# matrix_main_board.net
KiCad netlist of a schematic drawn in EAGLE
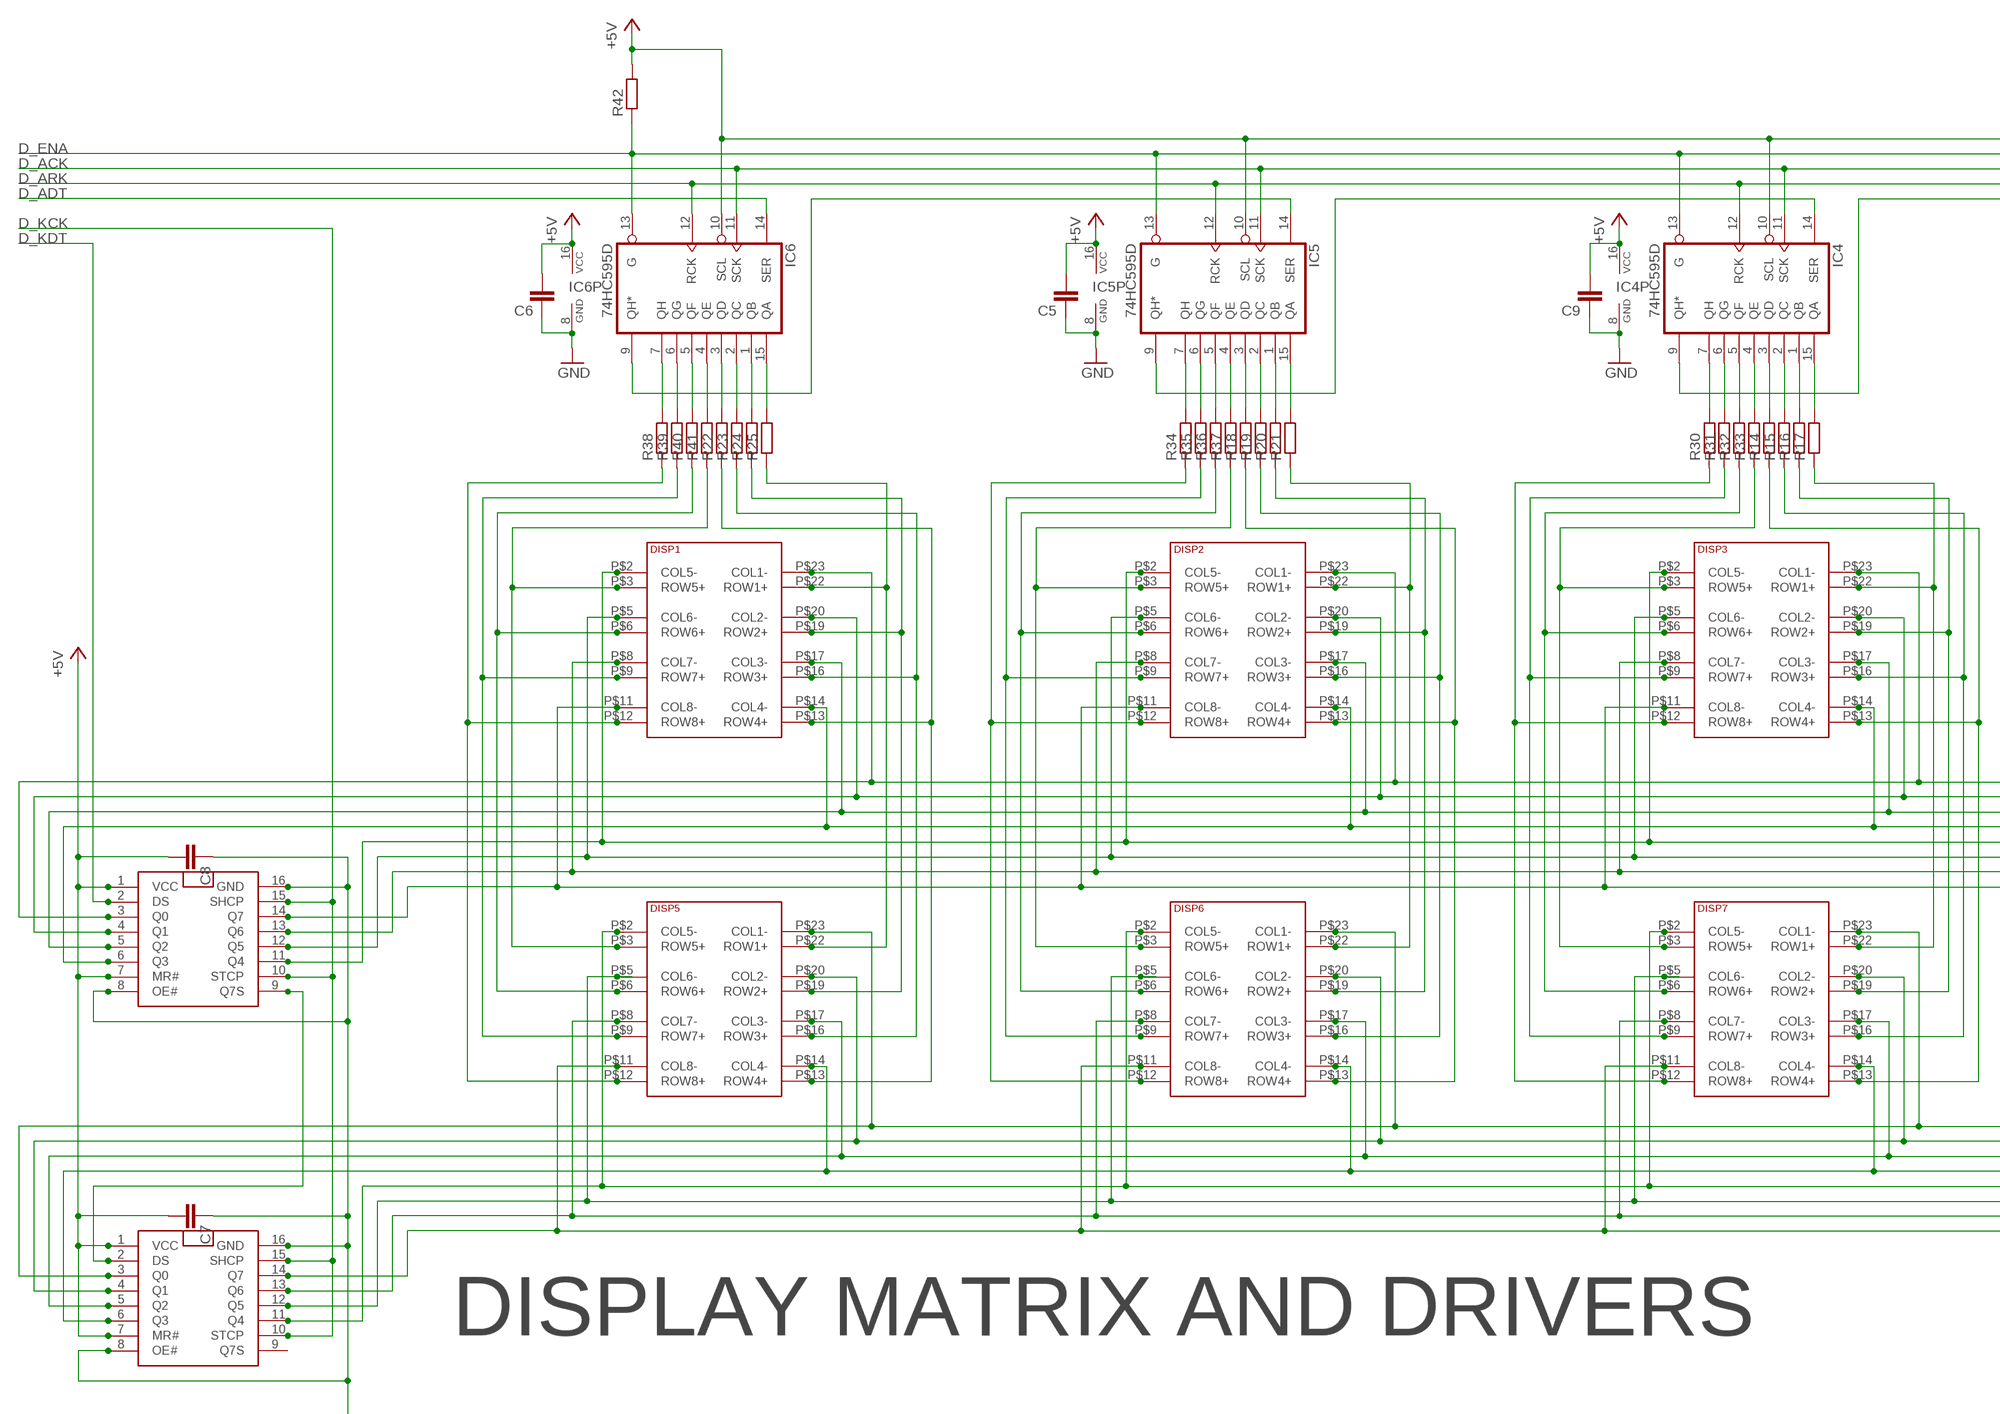
[diagram p0: schematic, sheet 1, part 1 of 3]
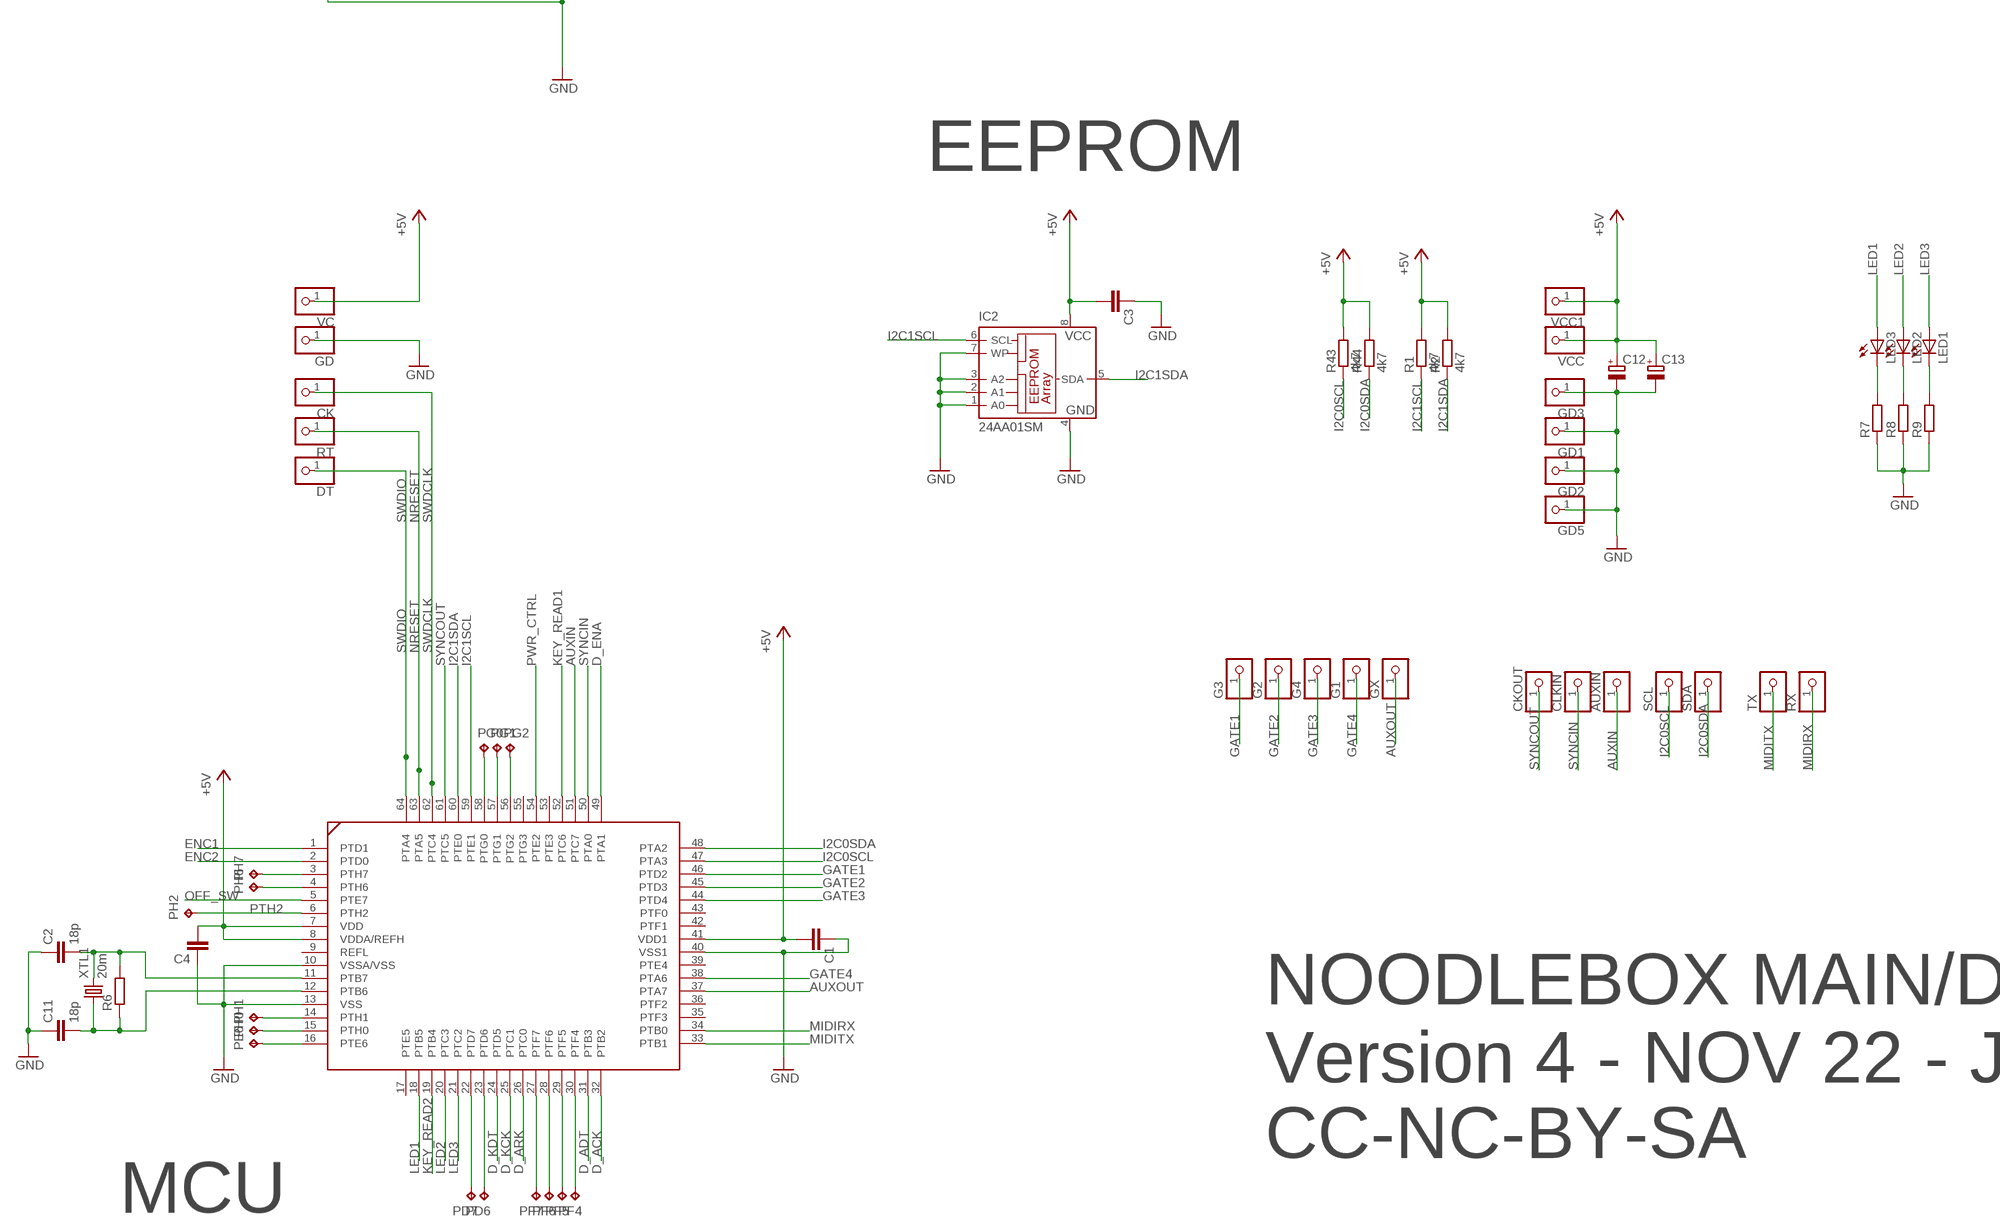
[diagram p1: schematic, sheet 1, part 2 of 3]
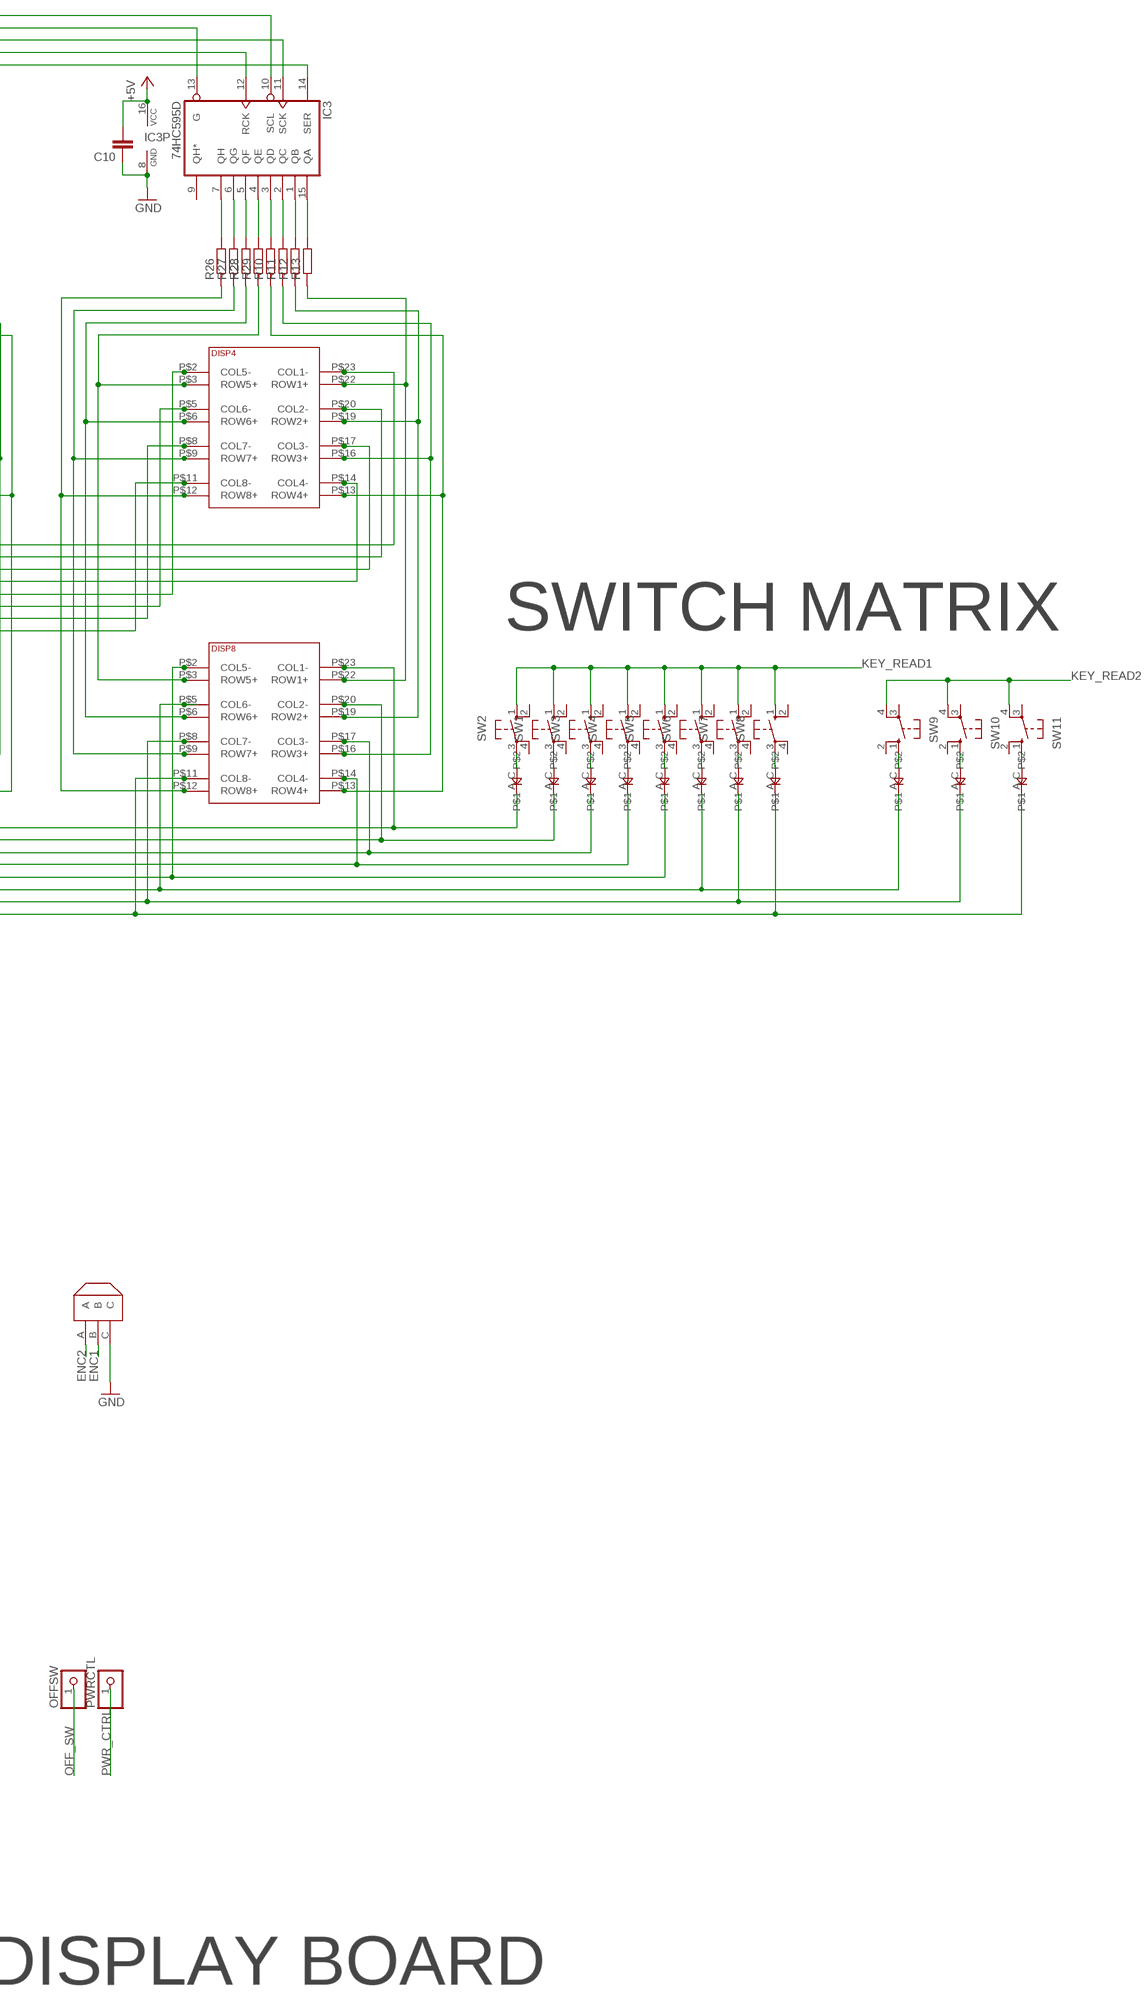
[diagram p2: schematic, sheet 1, part 3 of 3]

(export (version "E")
  (design (tool "Eeschema 10.0.6"))
  (components
    (comp (ref "AUXIN")
      (value "PINHD-1X1")
      (footprint "eagle-import:1X01")
      (libsource (lib "eagle-import") (part "PINHD-1X1"))
    )
    (comp (ref "C1")
      (value "C-EUC0805")
      (footprint "eagle-import:C0805")
      (libsource (lib "eagle-import") (part "C-EUC0805"))
    )
    (comp (ref "C2")
      (value "18p")
      (footprint "eagle-import:C0805")
      (libsource (lib "eagle-import") (part "C-EUC0805"))
    )
    (comp (ref "C3")
      (value "C-EUC0805")
      (footprint "eagle-import:C0805")
      (libsource (lib "eagle-import") (part "C-EUC0805"))
    )
    (comp (ref "C4")
      (value "C-EUC0805")
      (footprint "eagle-import:C0805")
      (libsource (lib "eagle-import") (part "C-EUC0805"))
    )
    (comp (ref "C5")
      (value "C-EUC0805")
      (footprint "eagle-import:C0805")
      (libsource (lib "eagle-import") (part "C-EUC0805"))
    )
    (comp (ref "C6")
      (value "C-EUC0805")
      (footprint "eagle-import:C0805")
      (libsource (lib "eagle-import") (part "C-EUC0805"))
    )
    (comp (ref "C7")
      (value "C-EUC0805")
      (footprint "eagle-import:C0805")
      (libsource (lib "eagle-import") (part "C-EUC0805"))
    )
    (comp (ref "C8")
      (value "C-EUC0805")
      (footprint "eagle-import:C0805")
      (libsource (lib "eagle-import") (part "C-EUC0805"))
    )
    (comp (ref "C9")
      (value "C-EUC0805")
      (footprint "eagle-import:C0805")
      (libsource (lib "eagle-import") (part "C-EUC0805"))
    )
    (comp (ref "C10")
      (value "C-EUC0805")
      (footprint "eagle-import:C0805")
      (libsource (lib "eagle-import") (part "C-EUC0805"))
    )
    (comp (ref "C11")
      (value "18p")
      (footprint "eagle-import:C0805")
      (libsource (lib "eagle-import") (part "C-EUC0805"))
    )
    (comp (ref "C12")
      (value "CPOL-EUE2.5-7")
      (footprint "eagle-import:E2,5-7")
      (libsource (lib "eagle-import") (part "CPOL-EUE2.5-7"))
    )
    (comp (ref "C13")
      (value "CPOL-EUE2.5-7")
      (footprint "eagle-import:E2,5-7")
      (libsource (lib "eagle-import") (part "CPOL-EUE2.5-7"))
    )
    (comp (ref "CK")
      (value "PINHD-1X1")
      (footprint "eagle-import:1X01")
      (libsource (lib "eagle-import") (part "PINHD-1X1"))
    )
    (comp (ref "CKOUT")
      (value "PINHD-1X1")
      (footprint "eagle-import:1X01")
      (libsource (lib "eagle-import") (part "PINHD-1X1"))
    )
    (comp (ref "CLKIN")
      (value "PINHD-1X1")
      (footprint "eagle-import:1X01")
      (libsource (lib "eagle-import") (part "PINHD-1X1"))
    )
    (comp (ref "D1")
      (value "0805DIODE")
      (footprint "eagle-import:0805DIODE")
      (libsource (lib "eagle-import") (part "0805DIODE"))
    )
    (comp (ref "D2")
      (value "0805DIODE")
      (footprint "eagle-import:0805DIODE")
      (libsource (lib "eagle-import") (part "0805DIODE"))
    )
    (comp (ref "D3")
      (value "0805DIODE")
      (footprint "eagle-import:0805DIODE")
      (libsource (lib "eagle-import") (part "0805DIODE"))
    )
    (comp (ref "D4")
      (value "0805DIODE")
      (footprint "eagle-import:0805DIODE")
      (libsource (lib "eagle-import") (part "0805DIODE"))
    )
    (comp (ref "D5")
      (value "0805DIODE")
      (footprint "eagle-import:0805DIODE")
      (libsource (lib "eagle-import") (part "0805DIODE"))
    )
    (comp (ref "D6")
      (value "0805DIODE")
      (footprint "eagle-import:0805DIODE")
      (libsource (lib "eagle-import") (part "0805DIODE"))
    )
    (comp (ref "D7")
      (value "0805DIODE")
      (footprint "eagle-import:0805DIODE")
      (libsource (lib "eagle-import") (part "0805DIODE"))
    )
    (comp (ref "D8")
      (value "0805DIODE")
      (footprint "eagle-import:0805DIODE")
      (libsource (lib "eagle-import") (part "0805DIODE"))
    )
    (comp (ref "D9")
      (value "0805DIODE")
      (footprint "eagle-import:0805DIODE")
      (libsource (lib "eagle-import") (part "0805DIODE"))
    )
    (comp (ref "D10")
      (value "0805DIODE")
      (footprint "eagle-import:0805DIODE")
      (libsource (lib "eagle-import") (part "0805DIODE"))
    )
    (comp (ref "D11")
      (value "0805DIODE")
      (footprint "eagle-import:0805DIODE")
      (libsource (lib "eagle-import") (part "0805DIODE"))
    )
    (comp (ref "DISP1")
      (value "1388BBMATRIX24PIN")
      (footprint "eagle-import:1388_24PIN")
      (libsource (lib "eagle-import") (part "1388BBMATRIX24PIN"))
    )
    (comp (ref "DISP2")
      (value "1388BBMATRIX24PIN")
      (footprint "eagle-import:1388_24PIN")
      (libsource (lib "eagle-import") (part "1388BBMATRIX24PIN"))
    )
    (comp (ref "DISP3")
      (value "1388BBMATRIX24PIN")
      (footprint "eagle-import:1388_24PIN")
      (libsource (lib "eagle-import") (part "1388BBMATRIX24PIN"))
    )
    (comp (ref "DISP4")
      (value "1388BBMATRIX24PIN")
      (footprint "eagle-import:1388_24PIN")
      (libsource (lib "eagle-import") (part "1388BBMATRIX24PIN"))
    )
    (comp (ref "DISP5")
      (value "1388BBMATRIX24PIN")
      (footprint "eagle-import:1388_24PIN")
      (libsource (lib "eagle-import") (part "1388BBMATRIX24PIN"))
    )
    (comp (ref "DISP6")
      (value "1388BBMATRIX24PIN")
      (footprint "eagle-import:1388_24PIN")
      (libsource (lib "eagle-import") (part "1388BBMATRIX24PIN"))
    )
    (comp (ref "DISP7")
      (value "1388BBMATRIX24PIN")
      (footprint "eagle-import:1388_24PIN")
      (libsource (lib "eagle-import") (part "1388BBMATRIX24PIN"))
    )
    (comp (ref "DISP8")
      (value "1388BBMATRIX24PIN")
      (footprint "eagle-import:1388_24PIN")
      (libsource (lib "eagle-import") (part "1388BBMATRIX24PIN"))
    )
    (comp (ref "DT")
      (value "PINHD-1X1")
      (footprint "eagle-import:1X01")
      (libsource (lib "eagle-import") (part "PINHD-1X1"))
    )
    (comp (ref "ENC1")
      (value "ENCODER")
      (footprint "eagle-import:ENCODER")
      (libsource (lib "eagle-import") (part "ENCODER"))
    )
    (comp (ref "G1")
      (value "PINHD-1X1")
      (footprint "eagle-import:1X01")
      (libsource (lib "eagle-import") (part "PINHD-1X1"))
    )
    (comp (ref "G2")
      (value "PINHD-1X1")
      (footprint "eagle-import:1X01")
      (libsource (lib "eagle-import") (part "PINHD-1X1"))
    )
    (comp (ref "G3")
      (value "PINHD-1X1")
      (footprint "eagle-import:1X01")
      (libsource (lib "eagle-import") (part "PINHD-1X1"))
    )
    (comp (ref "G4")
      (value "PINHD-1X1")
      (footprint "eagle-import:1X01")
      (libsource (lib "eagle-import") (part "PINHD-1X1"))
    )
    (comp (ref "GD")
      (value "PINHD-1X1")
      (footprint "eagle-import:1X01")
      (libsource (lib "eagle-import") (part "PINHD-1X1"))
    )
    (comp (ref "GD1")
      (value "PINHD-1X1")
      (footprint "eagle-import:1X01")
      (libsource (lib "eagle-import") (part "PINHD-1X1"))
    )
    (comp (ref "GD2")
      (value "PINHD-1X1")
      (footprint "eagle-import:1X01")
      (libsource (lib "eagle-import") (part "PINHD-1X1"))
    )
    (comp (ref "GD3")
      (value "PINHD-1X1")
      (footprint "eagle-import:1X01")
      (libsource (lib "eagle-import") (part "PINHD-1X1"))
    )
    (comp (ref "GD5")
      (value "PINHD-1X1")
      (footprint "eagle-import:1X01")
      (libsource (lib "eagle-import") (part "PINHD-1X1"))
    )
    (comp (ref "GX")
      (value "PINHD-1X1")
      (footprint "eagle-import:1X01")
      (libsource (lib "eagle-import") (part "PINHD-1X1"))
    )
    (comp (ref "IC1")
      (value "MKE02_64PINQFP64")
      (footprint "eagle-import:QFP64_SOT393")
      (libsource (lib "eagle-import") (part "MKE02_64PINQFP64"))
    )
    (comp (ref "IC2")
      (value "24AA01SM")
      (footprint "eagle-import:SO-08M")
      (fields (field (name "MF") "MICROCHIP") (field (name "MPN") "24AA01-I/SN"))
      (libsource (lib "eagle-import") (part "24SMAA01"))
    )
    (comp (ref "IC3")
      (value "74HC595D")
      (footprint "eagle-import:SO16")
      (libsource (lib "eagle-import") (part "74595DHC"))
    )
    (comp (ref "IC4")
      (value "74HC595D")
      (footprint "eagle-import:SO16")
      (libsource (lib "eagle-import") (part "74595DHC"))
    )
    (comp (ref "IC5")
      (value "74HC595D")
      (footprint "eagle-import:SO16")
      (libsource (lib "eagle-import") (part "74595DHC"))
    )
    (comp (ref "IC6")
      (value "74HC595D")
      (footprint "eagle-import:SO16")
      (libsource (lib "eagle-import") (part "74595DHC"))
    )
    (comp (ref "IC7")
      (value "NPIC6C596")
      (footprint "eagle-import:SO16")
      (libsource (lib "eagle-import") (part "NPIC6C596"))
    )
    (comp (ref "IC8")
      (value "NPIC6C596")
      (footprint "eagle-import:SO16")
      (libsource (lib "eagle-import") (part "NPIC6C596"))
    )
    (comp (ref "LED1")
      (value "LED3MM")
      (footprint "eagle-import:LED3MM")
      (libsource (lib "eagle-import") (part "LED3MM"))
    )
    (comp (ref "LED2")
      (value "LED3MM")
      (footprint "eagle-import:LED3MM")
      (libsource (lib "eagle-import") (part "LED3MM"))
    )
    (comp (ref "LED3")
      (value "LED3MM")
      (footprint "eagle-import:LED3MM")
      (libsource (lib "eagle-import") (part "LED3MM"))
    )
    (comp (ref "OFFSW")
      (value "PINHD-1X1")
      (footprint "eagle-import:1X01")
      (libsource (lib "eagle-import") (part "PINHD-1X1"))
    )
    (comp (ref "PD6")
      (value "TPTP17R")
      (footprint "eagle-import:TP17R")
      (libsource (lib "eagle-import") (part "TPTP17R"))
    )
    (comp (ref "PD7")
      (value "TPTP17R")
      (footprint "eagle-import:TP17R")
      (libsource (lib "eagle-import") (part "TPTP17R"))
    )
    (comp (ref "PE6")
      (value "TPTP17R")
      (footprint "eagle-import:TP17R")
      (libsource (lib "eagle-import") (part "TPTP17R"))
    )
    (comp (ref "PF4")
      (value "TPTP17R")
      (footprint "eagle-import:TP17R")
      (libsource (lib "eagle-import") (part "TPTP17R"))
    )
    (comp (ref "PF5")
      (value "TPTP17R")
      (footprint "eagle-import:TP17R")
      (libsource (lib "eagle-import") (part "TPTP17R"))
    )
    (comp (ref "PF6")
      (value "TPTP17R")
      (footprint "eagle-import:TP17R")
      (libsource (lib "eagle-import") (part "TPTP17R"))
    )
    (comp (ref "PF7")
      (value "TPTP17R")
      (footprint "eagle-import:TP17R")
      (libsource (lib "eagle-import") (part "TPTP17R"))
    )
    (comp (ref "PG0")
      (value "TPTP17R")
      (footprint "eagle-import:TP17R")
      (libsource (lib "eagle-import") (part "TPTP17R"))
    )
    (comp (ref "PG1")
      (value "TPTP17R")
      (footprint "eagle-import:TP17R")
      (libsource (lib "eagle-import") (part "TPTP17R"))
    )
    (comp (ref "PG2")
      (value "TPTP17R")
      (footprint "eagle-import:TP17R")
      (libsource (lib "eagle-import") (part "TPTP17R"))
    )
    (comp (ref "PH0")
      (value "TPTP17R")
      (footprint "eagle-import:TP17R")
      (libsource (lib "eagle-import") (part "TPTP17R"))
    )
    (comp (ref "PH1")
      (value "TPTP17R")
      (footprint "eagle-import:TP17R")
      (libsource (lib "eagle-import") (part "TPTP17R"))
    )
    (comp (ref "PH2")
      (value "TPTP17R")
      (footprint "eagle-import:TP17R")
      (libsource (lib "eagle-import") (part "TPTP17R"))
    )
    (comp (ref "PH6")
      (value "TPTP17R")
      (footprint "eagle-import:TP17R")
      (libsource (lib "eagle-import") (part "TPTP17R"))
    )
    (comp (ref "PH7")
      (value "TPTP17R")
      (footprint "eagle-import:TP17R")
      (libsource (lib "eagle-import") (part "TPTP17R"))
    )
    (comp (ref "PWRCTL")
      (value "PINHD-1X1")
      (footprint "eagle-import:1X01")
      (libsource (lib "eagle-import") (part "PINHD-1X1"))
    )
    (comp (ref "R1")
      (value "4k7")
      (footprint "eagle-import:R0805")
      (libsource (lib "eagle-import") (part "R-EU_R0805"))
    )
    (comp (ref "R2")
      (value "4k7")
      (footprint "eagle-import:R0805")
      (libsource (lib "eagle-import") (part "R-EU_R0805"))
    )
    (comp (ref "R6")
      (value "R-EU_R0805")
      (footprint "eagle-import:R0805")
      (libsource (lib "eagle-import") (part "R-EU_R0805"))
    )
    (comp (ref "R7")
      (value "R-EU_R0805")
      (footprint "eagle-import:R0805")
      (libsource (lib "eagle-import") (part "R-EU_R0805"))
    )
    (comp (ref "R8")
      (value "R-EU_R0805")
      (footprint "eagle-import:R0805")
      (libsource (lib "eagle-import") (part "R-EU_R0805"))
    )
    (comp (ref "R9")
      (value "R-EU_R0805")
      (footprint "eagle-import:R0805")
      (libsource (lib "eagle-import") (part "R-EU_R0805"))
    )
    (comp (ref "R10")
      (value "R-EU_R0805")
      (footprint "eagle-import:R0805")
      (libsource (lib "eagle-import") (part "R-EU_R0805"))
    )
    (comp (ref "R11")
      (value "R-EU_R0805")
      (footprint "eagle-import:R0805")
      (libsource (lib "eagle-import") (part "R-EU_R0805"))
    )
    (comp (ref "R12")
      (value "R-EU_R0805")
      (footprint "eagle-import:R0805")
      (libsource (lib "eagle-import") (part "R-EU_R0805"))
    )
    (comp (ref "R13")
      (value "R-EU_R0805")
      (footprint "eagle-import:R0805")
      (libsource (lib "eagle-import") (part "R-EU_R0805"))
    )
    (comp (ref "R14")
      (value "R-EU_R0805")
      (footprint "eagle-import:R0805")
      (libsource (lib "eagle-import") (part "R-EU_R0805"))
    )
    (comp (ref "R15")
      (value "R-EU_R0805")
      (footprint "eagle-import:R0805")
      (libsource (lib "eagle-import") (part "R-EU_R0805"))
    )
    (comp (ref "R16")
      (value "R-EU_R0805")
      (footprint "eagle-import:R0805")
      (libsource (lib "eagle-import") (part "R-EU_R0805"))
    )
    (comp (ref "R17")
      (value "R-EU_R0805")
      (footprint "eagle-import:R0805")
      (libsource (lib "eagle-import") (part "R-EU_R0805"))
    )
    (comp (ref "R18")
      (value "R-EU_R0805")
      (footprint "eagle-import:R0805")
      (libsource (lib "eagle-import") (part "R-EU_R0805"))
    )
    (comp (ref "R19")
      (value "R-EU_R0805")
      (footprint "eagle-import:R0805")
      (libsource (lib "eagle-import") (part "R-EU_R0805"))
    )
    (comp (ref "R20")
      (value "R-EU_R0805")
      (footprint "eagle-import:R0805")
      (libsource (lib "eagle-import") (part "R-EU_R0805"))
    )
    (comp (ref "R21")
      (value "R-EU_R0805")
      (footprint "eagle-import:R0805")
      (libsource (lib "eagle-import") (part "R-EU_R0805"))
    )
    (comp (ref "R22")
      (value "R-EU_R0805")
      (footprint "eagle-import:R0805")
      (libsource (lib "eagle-import") (part "R-EU_R0805"))
    )
    (comp (ref "R23")
      (value "R-EU_R0805")
      (footprint "eagle-import:R0805")
      (libsource (lib "eagle-import") (part "R-EU_R0805"))
    )
    (comp (ref "R24")
      (value "R-EU_R0805")
      (footprint "eagle-import:R0805")
      (libsource (lib "eagle-import") (part "R-EU_R0805"))
    )
    (comp (ref "R25")
      (value "R-EU_R0805")
      (footprint "eagle-import:R0805")
      (libsource (lib "eagle-import") (part "R-EU_R0805"))
    )
    (comp (ref "R26")
      (value "R-EU_R0805")
      (footprint "eagle-import:R0805")
      (libsource (lib "eagle-import") (part "R-EU_R0805"))
    )
    (comp (ref "R27")
      (value "R-EU_R0805")
      (footprint "eagle-import:R0805")
      (libsource (lib "eagle-import") (part "R-EU_R0805"))
    )
    (comp (ref "R28")
      (value "R-EU_R0805")
      (footprint "eagle-import:R0805")
      (libsource (lib "eagle-import") (part "R-EU_R0805"))
    )
    (comp (ref "R29")
      (value "R-EU_R0805")
      (footprint "eagle-import:R0805")
      (libsource (lib "eagle-import") (part "R-EU_R0805"))
    )
    (comp (ref "R30")
      (value "R-EU_R0805")
      (footprint "eagle-import:R0805")
      (libsource (lib "eagle-import") (part "R-EU_R0805"))
    )
    (comp (ref "R31")
      (value "R-EU_R0805")
      (footprint "eagle-import:R0805")
      (libsource (lib "eagle-import") (part "R-EU_R0805"))
    )
    (comp (ref "R32")
      (value "R-EU_R0805")
      (footprint "eagle-import:R0805")
      (libsource (lib "eagle-import") (part "R-EU_R0805"))
    )
    (comp (ref "R33")
      (value "R-EU_R0805")
      (footprint "eagle-import:R0805")
      (libsource (lib "eagle-import") (part "R-EU_R0805"))
    )
    (comp (ref "R34")
      (value "R-EU_R0805")
      (footprint "eagle-import:R0805")
      (libsource (lib "eagle-import") (part "R-EU_R0805"))
    )
    (comp (ref "R35")
      (value "R-EU_R0805")
      (footprint "eagle-import:R0805")
      (libsource (lib "eagle-import") (part "R-EU_R0805"))
    )
    (comp (ref "R36")
      (value "R-EU_R0805")
      (footprint "eagle-import:R0805")
      (libsource (lib "eagle-import") (part "R-EU_R0805"))
    )
    (comp (ref "R37")
      (value "R-EU_R0805")
      (footprint "eagle-import:R0805")
      (libsource (lib "eagle-import") (part "R-EU_R0805"))
    )
    (comp (ref "R38")
      (value "R-EU_R0805")
      (footprint "eagle-import:R0805")
      (libsource (lib "eagle-import") (part "R-EU_R0805"))
    )
    (comp (ref "R39")
      (value "R-EU_R0805")
      (footprint "eagle-import:R0805")
      (libsource (lib "eagle-import") (part "R-EU_R0805"))
    )
    (comp (ref "R40")
      (value "R-EU_R0805")
      (footprint "eagle-import:R0805")
      (libsource (lib "eagle-import") (part "R-EU_R0805"))
    )
    (comp (ref "R41")
      (value "R-EU_R0805")
      (footprint "eagle-import:R0805")
      (libsource (lib "eagle-import") (part "R-EU_R0805"))
    )
    (comp (ref "R42")
      (value "R-EU_R0805")
      (footprint "eagle-import:R0805")
      (libsource (lib "eagle-import") (part "R-EU_R0805"))
    )
    (comp (ref "R43")
      (value "4k7")
      (footprint "eagle-import:R0805")
      (libsource (lib "eagle-import") (part "R-EU_R0805"))
    )
    (comp (ref "R44")
      (value "4k7")
      (footprint "eagle-import:R0805")
      (libsource (lib "eagle-import") (part "R-EU_R0805"))
    )
    (comp (ref "RT")
      (value "PINHD-1X1")
      (footprint "eagle-import:1X01")
      (libsource (lib "eagle-import") (part "PINHD-1X1"))
    )
    (comp (ref "RX")
      (value "PINHD-1X1")
      (footprint "eagle-import:1X01")
      (libsource (lib "eagle-import") (part "PINHD-1X1"))
    )
    (comp (ref "SCL")
      (value "PINHD-1X1")
      (footprint "eagle-import:1X01")
      (libsource (lib "eagle-import") (part "PINHD-1X1"))
    )
    (comp (ref "SDA")
      (value "PINHD-1X1")
      (footprint "eagle-import:1X01")
      (libsource (lib "eagle-import") (part "PINHD-1X1"))
    )
    (comp (ref "SW1")
      (value "40-XX")
      (footprint "eagle-import:B3F-40XX")
      (fields (field (name "MF") "OMRON COMPONENTS USA") (field (name "MPN") "B3F-4000"))
      (libsource (lib "eagle-import") (part "40-XX"))
    )
    (comp (ref "SW2")
      (value "40-XX")
      (footprint "eagle-import:B3F-40XX")
      (fields (field (name "MF") "OMRON COMPONENTS USA") (field (name "MPN") "B3F-4000"))
      (libsource (lib "eagle-import") (part "40-XX"))
    )
    (comp (ref "SW3")
      (value "40-XX")
      (footprint "eagle-import:B3F-40XX")
      (fields (field (name "MF") "OMRON COMPONENTS USA") (field (name "MPN") "B3F-4000"))
      (libsource (lib "eagle-import") (part "40-XX"))
    )
    (comp (ref "SW4")
      (value "40-XX")
      (footprint "eagle-import:B3F-40XX")
      (fields (field (name "MF") "OMRON COMPONENTS USA") (field (name "MPN") "B3F-4000"))
      (libsource (lib "eagle-import") (part "40-XX"))
    )
    (comp (ref "SW5")
      (value "40-XX")
      (footprint "eagle-import:B3F-40XX")
      (fields (field (name "MF") "OMRON COMPONENTS USA") (field (name "MPN") "B3F-4000"))
      (libsource (lib "eagle-import") (part "40-XX"))
    )
    (comp (ref "SW6")
      (value "40-XX")
      (footprint "eagle-import:B3F-40XX")
      (fields (field (name "MF") "OMRON COMPONENTS USA") (field (name "MPN") "B3F-4000"))
      (libsource (lib "eagle-import") (part "40-XX"))
    )
    (comp (ref "SW7")
      (value "40-XX")
      (footprint "eagle-import:B3F-40XX")
      (fields (field (name "MF") "OMRON COMPONENTS USA") (field (name "MPN") "B3F-4000"))
      (libsource (lib "eagle-import") (part "40-XX"))
    )
    (comp (ref "SW8")
      (value "40-XX")
      (footprint "eagle-import:B3F-40XX")
      (fields (field (name "MF") "OMRON COMPONENTS USA") (field (name "MPN") "B3F-4000"))
      (libsource (lib "eagle-import") (part "40-XX"))
    )
    (comp (ref "SW9")
      (value "10-XX")
      (footprint "eagle-import:B3F-10XX")
      (fields (field (name "MPN") "B3F-1000"))
      (libsource (lib "eagle-import") (part "10-XX"))
    )
    (comp (ref "SW10")
      (value "10-XX")
      (footprint "eagle-import:B3F-10XX")
      (fields (field (name "MPN") "B3F-1000"))
      (libsource (lib "eagle-import") (part "10-XX"))
    )
    (comp (ref "SW11")
      (value "10-XX")
      (footprint "eagle-import:B3F-10XX")
      (fields (field (name "MPN") "B3F-1000"))
      (libsource (lib "eagle-import") (part "10-XX"))
    )
    (comp (ref "TX")
      (value "PINHD-1X1")
      (footprint "eagle-import:1X01")
      (libsource (lib "eagle-import") (part "PINHD-1X1"))
    )
    (comp (ref "VC")
      (value "PINHD-1X1")
      (footprint "eagle-import:1X01")
      (libsource (lib "eagle-import") (part "PINHD-1X1"))
    )
    (comp (ref "VCC")
      (value "PINHD-1X1")
      (footprint "eagle-import:1X01")
      (libsource (lib "eagle-import") (part "PINHD-1X1"))
    )
    (comp (ref "VCC1")
      (value "PINHD-1X1")
      (footprint "eagle-import:1X01")
      (libsource (lib "eagle-import") (part "PINHD-1X1"))
    )
    (comp (ref "XTL1")
      (value "20m")
      (footprint "eagle-import:HC49_S")
      (libsource (lib "eagle-import") (part "CRYSTALHC49S"))
    )
  )
  (nets
    (net (code "1") (name "+5V") (class "Default")
      (node (ref "C1") (pin "2") (pinfunction "2_2") (pintype "passive"))
      (node (ref "C10") (pin "2") (pinfunction "2_2") (pintype "passive"))
      (node (ref "C12") (pin "+") (pinfunction "+_+") (pintype "passive"))
      (node (ref "C13") (pin "+") (pinfunction "+_+") (pintype "passive"))
      (node (ref "C3") (pin "2") (pinfunction "2_2") (pintype "passive"))
      (node (ref "C4") (pin "2") (pinfunction "2_2") (pintype "passive"))
      (node (ref "C5") (pin "2") (pinfunction "2_2") (pintype "passive"))
      (node (ref "C6") (pin "2") (pinfunction "2_2") (pintype "passive"))
      (node (ref "C7") (pin "2") (pinfunction "2_2") (pintype "passive"))
      (node (ref "C8") (pin "2") (pinfunction "2_2") (pintype "passive"))
      (node (ref "C9") (pin "2") (pinfunction "2_2") (pintype "passive"))
      (node (ref "IC1") (pin "41") (pinfunction "VDD1_41") (pintype "power_in"))
      (node (ref "IC1") (pin "7") (pinfunction "VDD_7") (pintype "power_in"))
      (node (ref "IC1") (pin "8") (pinfunction "VDDA/REFH_8") (pintype "power_in"))
      (node (ref "IC2") (pin "8") (pinfunction "VCC_8") (pintype "power_in"))
      (node (ref "IC3") (pin "10") (pinfunction "SCL_10") (pintype "input"))
      (node (ref "IC3") (pin "16") (pinfunction "VCC_16") (pintype "power_in"))
      (node (ref "IC4") (pin "10") (pinfunction "SCL_10") (pintype "input"))
      (node (ref "IC4") (pin "16") (pinfunction "VCC_16") (pintype "power_in"))
      (node (ref "IC5") (pin "10") (pinfunction "SCL_10") (pintype "input"))
      (node (ref "IC5") (pin "16") (pinfunction "VCC_16") (pintype "power_in"))
      (node (ref "IC6") (pin "10") (pinfunction "SCL_10") (pintype "input"))
      (node (ref "IC6") (pin "16") (pinfunction "VCC_16") (pintype "power_in"))
      (node (ref "IC7") (pin "1") (pinfunction "VCC_1") (pintype "power_in"))
      (node (ref "IC7") (pin "7") (pinfunction "MR#_7") (pintype "input"))
      (node (ref "IC8") (pin "1") (pinfunction "VCC_1") (pintype "power_in"))
      (node (ref "IC8") (pin "7") (pinfunction "MR#_7") (pintype "input"))
      (node (ref "R1") (pin "2") (pinfunction "2_2") (pintype "passive"))
      (node (ref "R2") (pin "2") (pinfunction "2_2") (pintype "passive"))
      (node (ref "R42") (pin "2") (pinfunction "2_2") (pintype "passive"))
      (node (ref "R43") (pin "2") (pinfunction "2_2") (pintype "passive"))
      (node (ref "R44") (pin "2") (pinfunction "2_2") (pintype "passive"))
      (node (ref "VC") (pin "1") (pinfunction "1_1") (pintype "passive"))
      (node (ref "VCC") (pin "1") (pinfunction "1_1") (pintype "passive"))
      (node (ref "VCC1") (pin "1") (pinfunction "1_1") (pintype "passive"))
    )
    (net (code "2") (name "/AUXIN") (class "Default")
      (node (ref "AUXIN") (pin "1") (pinfunction "1_1") (pintype "passive"))
      (node (ref "IC1") (pin "51") (pinfunction "PTC7_51") (pintype "bidirectional"))
    )
    (net (code "3") (name "/AUXOUT") (class "Default")
      (node (ref "GX") (pin "1") (pinfunction "1_1") (pintype "passive"))
      (node (ref "IC1") (pin "37") (pinfunction "PTA7_37") (pintype "bidirectional"))
    )
    (net (code "4") (name "/D_ACK") (class "Default")
      (node (ref "IC1") (pin "32") (pinfunction "PTB2_32") (pintype "bidirectional"))
      (node (ref "IC3") (pin "11") (pinfunction "SCK_11") (pintype "input"))
      (node (ref "IC4") (pin "11") (pinfunction "SCK_11") (pintype "input"))
      (node (ref "IC5") (pin "11") (pinfunction "SCK_11") (pintype "input"))
      (node (ref "IC6") (pin "11") (pinfunction "SCK_11") (pintype "input"))
    )
    (net (code "5") (name "/D_ADT") (class "Default")
      (node (ref "IC1") (pin "31") (pinfunction "PTB3_31") (pintype "bidirectional"))
      (node (ref "IC6") (pin "14") (pinfunction "SER_14") (pintype "input"))
    )
    (net (code "6") (name "/D_ARK") (class "Default")
      (node (ref "IC1") (pin "26") (pinfunction "PTC0_26") (pintype "bidirectional"))
      (node (ref "IC3") (pin "12") (pinfunction "RCK_12") (pintype "input"))
      (node (ref "IC4") (pin "12") (pinfunction "RCK_12") (pintype "input"))
      (node (ref "IC5") (pin "12") (pinfunction "RCK_12") (pintype "input"))
      (node (ref "IC6") (pin "12") (pinfunction "RCK_12") (pintype "input"))
    )
    (net (code "7") (name "/D_ENA") (class "Default")
      (node (ref "IC1") (pin "49") (pinfunction "PTA1_49") (pintype "bidirectional"))
      (node (ref "IC3") (pin "13") (pinfunction "G_13") (pintype "input"))
      (node (ref "IC4") (pin "13") (pinfunction "G_13") (pintype "input"))
      (node (ref "IC5") (pin "13") (pinfunction "G_13") (pintype "input"))
      (node (ref "IC6") (pin "13") (pinfunction "G_13") (pintype "input"))
      (node (ref "R42") (pin "1") (pinfunction "1_1") (pintype "passive"))
    )
    (net (code "8") (name "/D_KCK") (class "Default")
      (node (ref "IC1") (pin "25") (pinfunction "PTC1_25") (pintype "bidirectional"))
      (node (ref "IC7") (pin "10") (pinfunction "STCP_10") (pintype "input"))
      (node (ref "IC7") (pin "15") (pinfunction "SHCP_15") (pintype "input"))
      (node (ref "IC8") (pin "10") (pinfunction "STCP_10") (pintype "input"))
      (node (ref "IC8") (pin "15") (pinfunction "SHCP_15") (pintype "input"))
    )
    (net (code "9") (name "/D_KDT") (class "Default")
      (node (ref "IC1") (pin "24") (pinfunction "PTD5_24") (pintype "bidirectional"))
      (node (ref "IC8") (pin "2") (pinfunction "DS_2") (pintype "input"))
    )
    (net (code "10") (name "/ENC1") (class "Default")
      (node (ref "ENC1") (pin "B") (pinfunction "B_B") (pintype "bidirectional"))
      (node (ref "IC1") (pin "1") (pinfunction "PTD1_1") (pintype "bidirectional"))
    )
    (net (code "11") (name "/ENC2") (class "Default")
      (node (ref "ENC1") (pin "A") (pinfunction "A_A") (pintype "bidirectional"))
      (node (ref "IC1") (pin "2") (pinfunction "PTD0_2") (pintype "bidirectional"))
    )
    (net (code "12") (name "/GATE1") (class "Default")
      (node (ref "G3") (pin "1") (pinfunction "1_1") (pintype "passive"))
      (node (ref "IC1") (pin "46") (pinfunction "PTD2_46") (pintype "bidirectional"))
    )
    (net (code "13") (name "/GATE2") (class "Default")
      (node (ref "G2") (pin "1") (pinfunction "1_1") (pintype "passive"))
      (node (ref "IC1") (pin "45") (pinfunction "PTD3_45") (pintype "bidirectional"))
    )
    (net (code "14") (name "/GATE3") (class "Default")
      (node (ref "G4") (pin "1") (pinfunction "1_1") (pintype "passive"))
      (node (ref "IC1") (pin "44") (pinfunction "PTD4_44") (pintype "bidirectional"))
    )
    (net (code "15") (name "/GATE4") (class "Default")
      (node (ref "G1") (pin "1") (pinfunction "1_1") (pintype "passive"))
      (node (ref "IC1") (pin "38") (pinfunction "PTA6_38") (pintype "bidirectional"))
    )
    (net (code "16") (name "/I2C0SCL") (class "Default")
      (node (ref "IC1") (pin "47") (pinfunction "PTA3_47") (pintype "bidirectional"))
      (node (ref "R43") (pin "1") (pinfunction "1_1") (pintype "passive"))
      (node (ref "SCL") (pin "1") (pinfunction "1_1") (pintype "passive"))
    )
    (net (code "17") (name "/I2C0SDA") (class "Default")
      (node (ref "IC1") (pin "48") (pinfunction "PTA2_48") (pintype "bidirectional"))
      (node (ref "R44") (pin "1") (pinfunction "1_1") (pintype "passive"))
      (node (ref "SDA") (pin "1") (pinfunction "1_1") (pintype "passive"))
    )
    (net (code "18") (name "/I2C1SCL") (class "Default")
      (node (ref "IC1") (pin "59") (pinfunction "PTE1_59") (pintype "bidirectional"))
      (node (ref "IC2") (pin "6") (pinfunction "SCL_6") (pintype "input"))
      (node (ref "R1") (pin "1") (pinfunction "1_1") (pintype "passive"))
    )
    (net (code "19") (name "/I2C1SDA") (class "Default")
      (node (ref "IC1") (pin "60") (pinfunction "PTE0_60") (pintype "bidirectional"))
      (node (ref "IC2") (pin "5") (pinfunction "SDA_5") (pintype "bidirectional"))
      (node (ref "R2") (pin "1") (pinfunction "1_1") (pintype "passive"))
    )
    (net (code "20") (name "/KEY_READ1") (class "Default")
      (node (ref "IC1") (pin "52") (pinfunction "PTC6_52") (pintype "bidirectional"))
      (node (ref "SW1") (pin "1") (pinfunction "S_1") (pintype "passive"))
      (node (ref "SW2") (pin "1") (pinfunction "S_1") (pintype "passive"))
      (node (ref "SW3") (pin "1") (pinfunction "S_1") (pintype "passive"))
      (node (ref "SW4") (pin "1") (pinfunction "S_1") (pintype "passive"))
      (node (ref "SW5") (pin "1") (pinfunction "S_1") (pintype "passive"))
      (node (ref "SW6") (pin "1") (pinfunction "S_1") (pintype "passive"))
      (node (ref "SW7") (pin "1") (pinfunction "S_1") (pintype "passive"))
      (node (ref "SW8") (pin "1") (pinfunction "S_1") (pintype "passive"))
    )
    (net (code "21") (name "/KEY_READ2") (class "Default")
      (node (ref "IC1") (pin "19") (pinfunction "PTB4_19") (pintype "bidirectional"))
      (node (ref "SW10") (pin "4") (pinfunction "P1_4") (pintype "passive"))
      (node (ref "SW11") (pin "4") (pinfunction "P1_4") (pintype "passive"))
      (node (ref "SW9") (pin "4") (pinfunction "P1_4") (pintype "passive"))
    )
    (net (code "22") (name "/LED1") (class "Default")
      (node (ref "IC1") (pin "18") (pinfunction "PTB5_18") (pintype "bidirectional"))
      (node (ref "LED3") (pin "A") (pinfunction "A_A") (pintype "passive"))
    )
    (net (code "23") (name "/LED2") (class "Default")
      (node (ref "IC1") (pin "20") (pinfunction "PTC3_20") (pintype "bidirectional"))
      (node (ref "LED2") (pin "A") (pinfunction "A_A") (pintype "passive"))
    )
    (net (code "24") (name "/LED3") (class "Default")
      (node (ref "IC1") (pin "21") (pinfunction "PTC2_21") (pintype "bidirectional"))
      (node (ref "LED1") (pin "A") (pinfunction "A_A") (pintype "passive"))
    )
    (net (code "25") (name "/MIDIRX") (class "Default")
      (node (ref "IC1") (pin "34") (pinfunction "PTB0_34") (pintype "bidirectional"))
      (node (ref "RX") (pin "1") (pinfunction "1_1") (pintype "passive"))
    )
    (net (code "26") (name "/MIDITX") (class "Default")
      (node (ref "IC1") (pin "33") (pinfunction "PTB1_33") (pintype "bidirectional"))
      (node (ref "TX") (pin "1") (pinfunction "1_1") (pintype "passive"))
    )
    (net (code "27") (name "/NRESET") (class "Default")
      (node (ref "IC1") (pin "63") (pinfunction "PTA5_63") (pintype "bidirectional"))
      (node (ref "RT") (pin "1") (pinfunction "1_1") (pintype "passive"))
    )
    (net (code "28") (name "/OFF_SW") (class "Default")
      (node (ref "IC1") (pin "5") (pinfunction "PTE7_5") (pintype "bidirectional"))
      (node (ref "OFFSW") (pin "1") (pinfunction "1_1") (pintype "passive"))
    )
    (net (code "29") (name "/PTH2") (class "Default")
      (node (ref "IC1") (pin "6") (pinfunction "PTH2_6") (pintype "bidirectional"))
      (node (ref "PH2") (pin "TP") (pinfunction "TP_TP") (pintype "input"))
    )
    (net (code "30") (name "/PWR_CTRL") (class "Default")
      (node (ref "IC1") (pin "54") (pinfunction "PTE2_54") (pintype "bidirectional"))
      (node (ref "PWRCTL") (pin "1") (pinfunction "1_1") (pintype "passive"))
    )
    (net (code "31") (name "/SWDCLK") (class "Default")
      (node (ref "CK") (pin "1") (pinfunction "1_1") (pintype "passive"))
      (node (ref "IC1") (pin "62") (pinfunction "PTC4_62") (pintype "bidirectional"))
    )
    (net (code "32") (name "/SWDIO") (class "Default")
      (node (ref "DT") (pin "1") (pinfunction "1_1") (pintype "passive"))
      (node (ref "IC1") (pin "64") (pinfunction "PTA4_64") (pintype "bidirectional"))
    )
    (net (code "33") (name "/SYNCIN") (class "Default")
      (node (ref "CLKIN") (pin "1") (pinfunction "1_1") (pintype "passive"))
      (node (ref "IC1") (pin "50") (pinfunction "PTA0_50") (pintype "bidirectional"))
    )
    (net (code "34") (name "/SYNCOUT") (class "Default")
      (node (ref "CKOUT") (pin "1") (pinfunction "1_1") (pintype "passive"))
      (node (ref "IC1") (pin "61") (pinfunction "PTC5_61") (pintype "bidirectional"))
    )
    (net (code "35") (name "GND") (class "Default")
      (node (ref "C1") (pin "1") (pinfunction "1_1") (pintype "passive"))
      (node (ref "C10") (pin "1") (pinfunction "1_1") (pintype "passive"))
      (node (ref "C11") (pin "1") (pinfunction "1_1") (pintype "passive"))
      (node (ref "C12") (pin "-") (pinfunction "-_-") (pintype "passive"))
      (node (ref "C13") (pin "-") (pinfunction "-_-") (pintype "passive"))
      (node (ref "C2") (pin "1") (pinfunction "1_1") (pintype "passive"))
      (node (ref "C3") (pin "1") (pinfunction "1_1") (pintype "passive"))
      (node (ref "C4") (pin "1") (pinfunction "1_1") (pintype "passive"))
      (node (ref "C5") (pin "1") (pinfunction "1_1") (pintype "passive"))
      (node (ref "C6") (pin "1") (pinfunction "1_1") (pintype "passive"))
      (node (ref "C7") (pin "1") (pinfunction "1_1") (pintype "passive"))
      (node (ref "C8") (pin "1") (pinfunction "1_1") (pintype "passive"))
      (node (ref "C9") (pin "1") (pinfunction "1_1") (pintype "passive"))
      (node (ref "ENC1") (pin "C") (pinfunction "C_C") (pintype "bidirectional"))
      (node (ref "GD") (pin "1") (pinfunction "1_1") (pintype "passive"))
      (node (ref "GD1") (pin "1") (pinfunction "1_1") (pintype "passive"))
      (node (ref "GD2") (pin "1") (pinfunction "1_1") (pintype "passive"))
      (node (ref "GD3") (pin "1") (pinfunction "1_1") (pintype "passive"))
      (node (ref "GD5") (pin "1") (pinfunction "1_1") (pintype "passive"))
      (node (ref "IC1") (pin "10") (pinfunction "VSSA/VSS_10") (pintype "power_in"))
      (node (ref "IC1") (pin "13") (pinfunction "VSS_13") (pintype "power_in"))
      (node (ref "IC1") (pin "40") (pinfunction "VSS1_40") (pintype "power_in"))
      (node (ref "IC2") (pin "1") (pinfunction "A0_1") (pintype "input"))
      (node (ref "IC2") (pin "2") (pinfunction "A1_2") (pintype "input"))
      (node (ref "IC2") (pin "3") (pinfunction "A2_3") (pintype "input"))
      (node (ref "IC2") (pin "4") (pinfunction "GND_4") (pintype "power_in"))
      (node (ref "IC2") (pin "7") (pinfunction "WP_7") (pintype "input"))
      (node (ref "IC3") (pin "8") (pinfunction "GND_8") (pintype "power_in"))
      (node (ref "IC4") (pin "8") (pinfunction "GND_8") (pintype "power_in"))
      (node (ref "IC5") (pin "8") (pinfunction "GND_8") (pintype "power_in"))
      (node (ref "IC6") (pin "8") (pinfunction "GND_8") (pintype "power_in"))
      (node (ref "IC7") (pin "16") (pinfunction "GND_16") (pintype "power_in"))
      (node (ref "IC7") (pin "8") (pinfunction "OE#_8") (pintype "input"))
      (node (ref "IC8") (pin "16") (pinfunction "GND_16") (pintype "power_in"))
      (node (ref "IC8") (pin "8") (pinfunction "OE#_8") (pintype "input"))
      (node (ref "R7") (pin "1") (pinfunction "1_1") (pintype "passive"))
      (node (ref "R8") (pin "1") (pinfunction "1_1") (pintype "passive"))
      (node (ref "R9") (pin "1") (pinfunction "1_1") (pintype "passive"))
    )
    (net (code "36") (name "Net-(D1-P$1)") (class "Default")
      (node (ref "D1") (pin "C") (pinfunction "P$1_C") (pintype "bidirectional"))
      (node (ref "SW8") (pin "3") (pinfunction "P_3") (pintype "passive"))
    )
    (net (code "37") (name "Net-(D1-P$2)") (class "Default")
      (node (ref "D1") (pin "A") (pinfunction "P$2_A") (pintype "bidirectional"))
      (node (ref "D9") (pin "A") (pinfunction "P$2_A") (pintype "bidirectional"))
      (node (ref "DISP5") (pin "P$11") (pinfunction "COL8-_P$11") (pintype "bidirectional"))
      (node (ref "DISP6") (pin "P$11") (pinfunction "COL8-_P$11") (pintype "bidirectional"))
      (node (ref "DISP7") (pin "P$11") (pinfunction "COL8-_P$11") (pintype "bidirectional"))
      (node (ref "DISP8") (pin "P$11") (pinfunction "COL8-_P$11") (pintype "bidirectional"))
      (node (ref "IC7") (pin "14") (pinfunction "Q7_14") (pintype "open_collector"))
    )
    (net (code "38") (name "Net-(D2-P$1)") (class "Default")
      (node (ref "D2") (pin "C") (pinfunction "P$1_C") (pintype "bidirectional"))
      (node (ref "SW7") (pin "3") (pinfunction "P_3") (pintype "passive"))
    )
    (net (code "39") (name "Net-(D3-P$1)") (class "Default")
      (node (ref "D3") (pin "C") (pinfunction "P$1_C") (pintype "bidirectional"))
      (node (ref "SW6") (pin "3") (pinfunction "P_3") (pintype "passive"))
    )
    (net (code "40") (name "Net-(D4-P$1)") (class "Default")
      (node (ref "D4") (pin "C") (pinfunction "P$1_C") (pintype "bidirectional"))
      (node (ref "SW5") (pin "3") (pinfunction "P_3") (pintype "passive"))
    )
    (net (code "41") (name "Net-(D4-P$2)") (class "Default")
      (node (ref "D4") (pin "A") (pinfunction "P$2_A") (pintype "bidirectional"))
      (node (ref "DISP5") (pin "P$2") (pinfunction "COL5-_P$2") (pintype "bidirectional"))
      (node (ref "DISP6") (pin "P$2") (pinfunction "COL5-_P$2") (pintype "bidirectional"))
      (node (ref "DISP7") (pin "P$2") (pinfunction "COL5-_P$2") (pintype "bidirectional"))
      (node (ref "DISP8") (pin "P$2") (pinfunction "COL5-_P$2") (pintype "bidirectional"))
      (node (ref "IC7") (pin "11") (pinfunction "Q4_11") (pintype "open_collector"))
    )
    (net (code "42") (name "Net-(D5-P$1)") (class "Default")
      (node (ref "D5") (pin "C") (pinfunction "P$1_C") (pintype "bidirectional"))
      (node (ref "SW4") (pin "3") (pinfunction "P_3") (pintype "passive"))
    )
    (net (code "43") (name "Net-(D5-P$2)") (class "Default")
      (node (ref "D5") (pin "A") (pinfunction "P$2_A") (pintype "bidirectional"))
      (node (ref "DISP5") (pin "P$14") (pinfunction "COL4-_P$14") (pintype "bidirectional"))
      (node (ref "DISP6") (pin "P$14") (pinfunction "COL4-_P$14") (pintype "bidirectional"))
      (node (ref "DISP7") (pin "P$14") (pinfunction "COL4-_P$14") (pintype "bidirectional"))
      (node (ref "DISP8") (pin "P$14") (pinfunction "COL4-_P$14") (pintype "bidirectional"))
      (node (ref "IC7") (pin "6") (pinfunction "Q3_6") (pintype "open_collector"))
    )
    (net (code "44") (name "Net-(D6-P$1)") (class "Default")
      (node (ref "D6") (pin "C") (pinfunction "P$1_C") (pintype "bidirectional"))
      (node (ref "SW3") (pin "3") (pinfunction "P_3") (pintype "passive"))
    )
    (net (code "45") (name "Net-(D6-P$2)") (class "Default")
      (node (ref "D6") (pin "A") (pinfunction "P$2_A") (pintype "bidirectional"))
      (node (ref "DISP5") (pin "P$17") (pinfunction "COL3-_P$17") (pintype "bidirectional"))
      (node (ref "DISP6") (pin "P$17") (pinfunction "COL3-_P$17") (pintype "bidirectional"))
      (node (ref "DISP7") (pin "P$17") (pinfunction "COL3-_P$17") (pintype "bidirectional"))
      (node (ref "DISP8") (pin "P$17") (pinfunction "COL3-_P$17") (pintype "bidirectional"))
      (node (ref "IC7") (pin "5") (pinfunction "Q2_5") (pintype "open_collector"))
    )
    (net (code "46") (name "Net-(D7-P$1)") (class "Default")
      (node (ref "D7") (pin "C") (pinfunction "P$1_C") (pintype "bidirectional"))
      (node (ref "SW2") (pin "3") (pinfunction "P_3") (pintype "passive"))
    )
    (net (code "47") (name "Net-(D7-P$2)") (class "Default")
      (node (ref "D7") (pin "A") (pinfunction "P$2_A") (pintype "bidirectional"))
      (node (ref "DISP5") (pin "P$23") (pinfunction "COL1-_P$23") (pintype "bidirectional"))
      (node (ref "DISP6") (pin "P$23") (pinfunction "COL1-_P$23") (pintype "bidirectional"))
      (node (ref "DISP7") (pin "P$23") (pinfunction "COL1-_P$23") (pintype "bidirectional"))
      (node (ref "DISP8") (pin "P$23") (pinfunction "COL1-_P$23") (pintype "bidirectional"))
      (node (ref "IC7") (pin "3") (pinfunction "Q0_3") (pintype "open_collector"))
    )
    (net (code "48") (name "Net-(D8-P$1)") (class "Default")
      (node (ref "D8") (pin "C") (pinfunction "P$1_C") (pintype "bidirectional"))
      (node (ref "SW1") (pin "3") (pinfunction "P_3") (pintype "passive"))
    )
    (net (code "49") (name "Net-(D8-P$2)") (class "Default")
      (node (ref "D8") (pin "A") (pinfunction "P$2_A") (pintype "bidirectional"))
      (node (ref "DISP5") (pin "P$20") (pinfunction "COL2-_P$20") (pintype "bidirectional"))
      (node (ref "DISP6") (pin "P$20") (pinfunction "COL2-_P$20") (pintype "bidirectional"))
      (node (ref "DISP7") (pin "P$20") (pinfunction "COL2-_P$20") (pintype "bidirectional"))
      (node (ref "DISP8") (pin "P$20") (pinfunction "COL2-_P$20") (pintype "bidirectional"))
      (node (ref "IC7") (pin "4") (pinfunction "Q1_4") (pintype "open_collector"))
    )
    (net (code "50") (name "Net-(D9-P$1)") (class "Default")
      (node (ref "D9") (pin "C") (pinfunction "P$1_C") (pintype "bidirectional"))
      (node (ref "SW11") (pin "1") (pinfunction "S_1") (pintype "passive"))
    )
    (net (code "51") (name "Net-(D10-P$1)") (class "Default")
      (node (ref "D10") (pin "C") (pinfunction "P$1_C") (pintype "bidirectional"))
      (node (ref "SW10") (pin "1") (pinfunction "S_1") (pintype "passive"))
    )
    (net (code "52") (name "Net-(D10-P$2)") (class "Default")
      (node (ref "D10") (pin "A") (pinfunction "P$2_A") (pintype "bidirectional"))
      (node (ref "D2") (pin "A") (pinfunction "P$2_A") (pintype "bidirectional"))
      (node (ref "DISP5") (pin "P$8") (pinfunction "COL7-_P$8") (pintype "bidirectional"))
      (node (ref "DISP6") (pin "P$8") (pinfunction "COL7-_P$8") (pintype "bidirectional"))
      (node (ref "DISP7") (pin "P$8") (pinfunction "COL7-_P$8") (pintype "bidirectional"))
      (node (ref "DISP8") (pin "P$8") (pinfunction "COL7-_P$8") (pintype "bidirectional"))
      (node (ref "IC7") (pin "13") (pinfunction "Q6_13") (pintype "open_collector"))
    )
    (net (code "53") (name "Net-(D11-P$1)") (class "Default")
      (node (ref "D11") (pin "C") (pinfunction "P$1_C") (pintype "bidirectional"))
      (node (ref "SW9") (pin "1") (pinfunction "S_1") (pintype "passive"))
    )
    (net (code "54") (name "Net-(D11-P$2)") (class "Default")
      (node (ref "D11") (pin "A") (pinfunction "P$2_A") (pintype "bidirectional"))
      (node (ref "D3") (pin "A") (pinfunction "P$2_A") (pintype "bidirectional"))
      (node (ref "DISP5") (pin "P$5") (pinfunction "COL6-_P$5") (pintype "bidirectional"))
      (node (ref "DISP6") (pin "P$5") (pinfunction "COL6-_P$5") (pintype "bidirectional"))
      (node (ref "DISP7") (pin "P$5") (pinfunction "COL6-_P$5") (pintype "bidirectional"))
      (node (ref "DISP8") (pin "P$5") (pinfunction "COL6-_P$5") (pintype "bidirectional"))
      (node (ref "IC7") (pin "12") (pinfunction "Q5_12") (pintype "open_collector"))
    )
    (net (code "55") (name "Net-(DISP1-COL1-)") (class "Default")
      (node (ref "DISP1") (pin "P$23") (pinfunction "COL1-_P$23") (pintype "bidirectional"))
      (node (ref "DISP2") (pin "P$23") (pinfunction "COL1-_P$23") (pintype "bidirectional"))
      (node (ref "DISP3") (pin "P$23") (pinfunction "COL1-_P$23") (pintype "bidirectional"))
      (node (ref "DISP4") (pin "P$23") (pinfunction "COL1-_P$23") (pintype "bidirectional"))
      (node (ref "IC8") (pin "3") (pinfunction "Q0_3") (pintype "open_collector"))
    )
    (net (code "56") (name "Net-(DISP1-COL2-)") (class "Default")
      (node (ref "DISP1") (pin "P$20") (pinfunction "COL2-_P$20") (pintype "bidirectional"))
      (node (ref "DISP2") (pin "P$20") (pinfunction "COL2-_P$20") (pintype "bidirectional"))
      (node (ref "DISP3") (pin "P$20") (pinfunction "COL2-_P$20") (pintype "bidirectional"))
      (node (ref "DISP4") (pin "P$20") (pinfunction "COL2-_P$20") (pintype "bidirectional"))
      (node (ref "IC8") (pin "4") (pinfunction "Q1_4") (pintype "open_collector"))
    )
    (net (code "57") (name "Net-(DISP1-COL3-)") (class "Default")
      (node (ref "DISP1") (pin "P$17") (pinfunction "COL3-_P$17") (pintype "bidirectional"))
      (node (ref "DISP2") (pin "P$17") (pinfunction "COL3-_P$17") (pintype "bidirectional"))
      (node (ref "DISP3") (pin "P$17") (pinfunction "COL3-_P$17") (pintype "bidirectional"))
      (node (ref "DISP4") (pin "P$17") (pinfunction "COL3-_P$17") (pintype "bidirectional"))
      (node (ref "IC8") (pin "5") (pinfunction "Q2_5") (pintype "open_collector"))
    )
    (net (code "58") (name "Net-(DISP1-COL4-)") (class "Default")
      (node (ref "DISP1") (pin "P$14") (pinfunction "COL4-_P$14") (pintype "bidirectional"))
      (node (ref "DISP2") (pin "P$14") (pinfunction "COL4-_P$14") (pintype "bidirectional"))
      (node (ref "DISP3") (pin "P$14") (pinfunction "COL4-_P$14") (pintype "bidirectional"))
      (node (ref "DISP4") (pin "P$14") (pinfunction "COL4-_P$14") (pintype "bidirectional"))
      (node (ref "IC8") (pin "6") (pinfunction "Q3_6") (pintype "open_collector"))
    )
    (net (code "59") (name "Net-(DISP1-COL5-)") (class "Default")
      (node (ref "DISP1") (pin "P$2") (pinfunction "COL5-_P$2") (pintype "bidirectional"))
      (node (ref "DISP2") (pin "P$2") (pinfunction "COL5-_P$2") (pintype "bidirectional"))
      (node (ref "DISP3") (pin "P$2") (pinfunction "COL5-_P$2") (pintype "bidirectional"))
      (node (ref "DISP4") (pin "P$2") (pinfunction "COL5-_P$2") (pintype "bidirectional"))
      (node (ref "IC8") (pin "11") (pinfunction "Q4_11") (pintype "open_collector"))
    )
    (net (code "60") (name "Net-(DISP1-COL6-)") (class "Default")
      (node (ref "DISP1") (pin "P$5") (pinfunction "COL6-_P$5") (pintype "bidirectional"))
      (node (ref "DISP2") (pin "P$5") (pinfunction "COL6-_P$5") (pintype "bidirectional"))
      (node (ref "DISP3") (pin "P$5") (pinfunction "COL6-_P$5") (pintype "bidirectional"))
      (node (ref "DISP4") (pin "P$5") (pinfunction "COL6-_P$5") (pintype "bidirectional"))
      (node (ref "IC8") (pin "12") (pinfunction "Q5_12") (pintype "open_collector"))
    )
    (net (code "61") (name "Net-(DISP1-COL7-)") (class "Default")
      (node (ref "DISP1") (pin "P$8") (pinfunction "COL7-_P$8") (pintype "bidirectional"))
      (node (ref "DISP2") (pin "P$8") (pinfunction "COL7-_P$8") (pintype "bidirectional"))
      (node (ref "DISP3") (pin "P$8") (pinfunction "COL7-_P$8") (pintype "bidirectional"))
      (node (ref "DISP4") (pin "P$8") (pinfunction "COL7-_P$8") (pintype "bidirectional"))
      (node (ref "IC8") (pin "13") (pinfunction "Q6_13") (pintype "open_collector"))
    )
    (net (code "62") (name "Net-(DISP1-COL8-)") (class "Default")
      (node (ref "DISP1") (pin "P$11") (pinfunction "COL8-_P$11") (pintype "bidirectional"))
      (node (ref "DISP2") (pin "P$11") (pinfunction "COL8-_P$11") (pintype "bidirectional"))
      (node (ref "DISP3") (pin "P$11") (pinfunction "COL8-_P$11") (pintype "bidirectional"))
      (node (ref "DISP4") (pin "P$11") (pinfunction "COL8-_P$11") (pintype "bidirectional"))
      (node (ref "IC8") (pin "14") (pinfunction "Q7_14") (pintype "open_collector"))
    )
    (net (code "63") (name "Net-(DISP1-ROW1+)") (class "Default")
      (node (ref "DISP1") (pin "P$22") (pinfunction "ROW1+_P$22") (pintype "bidirectional"))
      (node (ref "DISP5") (pin "P$22") (pinfunction "ROW1+_P$22") (pintype "bidirectional"))
      (node (ref "R25") (pin "1") (pinfunction "1_1") (pintype "passive"))
    )
    (net (code "64") (name "Net-(DISP1-ROW2+)") (class "Default")
      (node (ref "DISP1") (pin "P$19") (pinfunction "ROW2+_P$19") (pintype "bidirectional"))
      (node (ref "DISP5") (pin "P$19") (pinfunction "ROW2+_P$19") (pintype "bidirectional"))
      (node (ref "R24") (pin "1") (pinfunction "1_1") (pintype "passive"))
    )
    (net (code "65") (name "Net-(DISP1-ROW3+)") (class "Default")
      (node (ref "DISP1") (pin "P$16") (pinfunction "ROW3+_P$16") (pintype "bidirectional"))
      (node (ref "DISP5") (pin "P$16") (pinfunction "ROW3+_P$16") (pintype "bidirectional"))
      (node (ref "R23") (pin "1") (pinfunction "1_1") (pintype "passive"))
    )
    (net (code "66") (name "Net-(DISP1-ROW4+)") (class "Default")
      (node (ref "DISP1") (pin "P$13") (pinfunction "ROW4+_P$13") (pintype "bidirectional"))
      (node (ref "DISP5") (pin "P$13") (pinfunction "ROW4+_P$13") (pintype "bidirectional"))
      (node (ref "R22") (pin "1") (pinfunction "1_1") (pintype "passive"))
    )
    (net (code "67") (name "Net-(DISP1-ROW5+)") (class "Default")
      (node (ref "DISP1") (pin "P$3") (pinfunction "ROW5+_P$3") (pintype "bidirectional"))
      (node (ref "DISP5") (pin "P$3") (pinfunction "ROW5+_P$3") (pintype "bidirectional"))
      (node (ref "R41") (pin "1") (pinfunction "1_1") (pintype "passive"))
    )
    (net (code "68") (name "Net-(DISP1-ROW6+)") (class "Default")
      (node (ref "DISP1") (pin "P$6") (pinfunction "ROW6+_P$6") (pintype "bidirectional"))
      (node (ref "DISP5") (pin "P$6") (pinfunction "ROW6+_P$6") (pintype "bidirectional"))
      (node (ref "R40") (pin "1") (pinfunction "1_1") (pintype "passive"))
    )
    (net (code "69") (name "Net-(DISP1-ROW7+)") (class "Default")
      (node (ref "DISP1") (pin "P$9") (pinfunction "ROW7+_P$9") (pintype "bidirectional"))
      (node (ref "DISP5") (pin "P$9") (pinfunction "ROW7+_P$9") (pintype "bidirectional"))
      (node (ref "R39") (pin "1") (pinfunction "1_1") (pintype "passive"))
    )
    (net (code "70") (name "Net-(DISP1-ROW8+)") (class "Default")
      (node (ref "DISP1") (pin "P$12") (pinfunction "ROW8+_P$12") (pintype "bidirectional"))
      (node (ref "DISP5") (pin "P$12") (pinfunction "ROW8+_P$12") (pintype "bidirectional"))
      (node (ref "R38") (pin "1") (pinfunction "1_1") (pintype "passive"))
    )
    (net (code "71") (name "Net-(DISP2-ROW1+)") (class "Default")
      (node (ref "DISP2") (pin "P$22") (pinfunction "ROW1+_P$22") (pintype "bidirectional"))
      (node (ref "DISP6") (pin "P$22") (pinfunction "ROW1+_P$22") (pintype "bidirectional"))
      (node (ref "R21") (pin "1") (pinfunction "1_1") (pintype "passive"))
    )
    (net (code "72") (name "Net-(DISP2-ROW2+)") (class "Default")
      (node (ref "DISP2") (pin "P$19") (pinfunction "ROW2+_P$19") (pintype "bidirectional"))
      (node (ref "DISP6") (pin "P$19") (pinfunction "ROW2+_P$19") (pintype "bidirectional"))
      (node (ref "R20") (pin "1") (pinfunction "1_1") (pintype "passive"))
    )
    (net (code "73") (name "Net-(DISP2-ROW3+)") (class "Default")
      (node (ref "DISP2") (pin "P$16") (pinfunction "ROW3+_P$16") (pintype "bidirectional"))
      (node (ref "DISP6") (pin "P$16") (pinfunction "ROW3+_P$16") (pintype "bidirectional"))
      (node (ref "R19") (pin "1") (pinfunction "1_1") (pintype "passive"))
    )
    (net (code "74") (name "Net-(DISP2-ROW4+)") (class "Default")
      (node (ref "DISP2") (pin "P$13") (pinfunction "ROW4+_P$13") (pintype "bidirectional"))
      (node (ref "DISP6") (pin "P$13") (pinfunction "ROW4+_P$13") (pintype "bidirectional"))
      (node (ref "R18") (pin "1") (pinfunction "1_1") (pintype "passive"))
    )
    (net (code "75") (name "Net-(DISP2-ROW5+)") (class "Default")
      (node (ref "DISP2") (pin "P$3") (pinfunction "ROW5+_P$3") (pintype "bidirectional"))
      (node (ref "DISP6") (pin "P$3") (pinfunction "ROW5+_P$3") (pintype "bidirectional"))
      (node (ref "R37") (pin "1") (pinfunction "1_1") (pintype "passive"))
    )
    (net (code "76") (name "Net-(DISP2-ROW6+)") (class "Default")
      (node (ref "DISP2") (pin "P$6") (pinfunction "ROW6+_P$6") (pintype "bidirectional"))
      (node (ref "DISP6") (pin "P$6") (pinfunction "ROW6+_P$6") (pintype "bidirectional"))
      (node (ref "R36") (pin "1") (pinfunction "1_1") (pintype "passive"))
    )
    (net (code "77") (name "Net-(DISP2-ROW7+)") (class "Default")
      (node (ref "DISP2") (pin "P$9") (pinfunction "ROW7+_P$9") (pintype "bidirectional"))
      (node (ref "DISP6") (pin "P$9") (pinfunction "ROW7+_P$9") (pintype "bidirectional"))
      (node (ref "R35") (pin "1") (pinfunction "1_1") (pintype "passive"))
    )
    (net (code "78") (name "Net-(DISP2-ROW8+)") (class "Default")
      (node (ref "DISP2") (pin "P$12") (pinfunction "ROW8+_P$12") (pintype "bidirectional"))
      (node (ref "DISP6") (pin "P$12") (pinfunction "ROW8+_P$12") (pintype "bidirectional"))
      (node (ref "R34") (pin "1") (pinfunction "1_1") (pintype "passive"))
    )
    (net (code "79") (name "Net-(DISP3-ROW1+)") (class "Default")
      (node (ref "DISP3") (pin "P$22") (pinfunction "ROW1+_P$22") (pintype "bidirectional"))
      (node (ref "DISP7") (pin "P$22") (pinfunction "ROW1+_P$22") (pintype "bidirectional"))
      (node (ref "R17") (pin "1") (pinfunction "1_1") (pintype "passive"))
    )
    (net (code "80") (name "Net-(DISP3-ROW2+)") (class "Default")
      (node (ref "DISP3") (pin "P$19") (pinfunction "ROW2+_P$19") (pintype "bidirectional"))
      (node (ref "DISP7") (pin "P$19") (pinfunction "ROW2+_P$19") (pintype "bidirectional"))
      (node (ref "R16") (pin "1") (pinfunction "1_1") (pintype "passive"))
    )
    (net (code "81") (name "Net-(DISP3-ROW3+)") (class "Default")
      (node (ref "DISP3") (pin "P$16") (pinfunction "ROW3+_P$16") (pintype "bidirectional"))
      (node (ref "DISP7") (pin "P$16") (pinfunction "ROW3+_P$16") (pintype "bidirectional"))
      (node (ref "R15") (pin "1") (pinfunction "1_1") (pintype "passive"))
    )
    (net (code "82") (name "Net-(DISP3-ROW4+)") (class "Default")
      (node (ref "DISP3") (pin "P$13") (pinfunction "ROW4+_P$13") (pintype "bidirectional"))
      (node (ref "DISP7") (pin "P$13") (pinfunction "ROW4+_P$13") (pintype "bidirectional"))
      (node (ref "R14") (pin "1") (pinfunction "1_1") (pintype "passive"))
    )
    (net (code "83") (name "Net-(DISP3-ROW5+)") (class "Default")
      (node (ref "DISP3") (pin "P$3") (pinfunction "ROW5+_P$3") (pintype "bidirectional"))
      (node (ref "DISP7") (pin "P$3") (pinfunction "ROW5+_P$3") (pintype "bidirectional"))
      (node (ref "R33") (pin "1") (pinfunction "1_1") (pintype "passive"))
    )
    (net (code "84") (name "Net-(DISP3-ROW6+)") (class "Default")
      (node (ref "DISP3") (pin "P$6") (pinfunction "ROW6+_P$6") (pintype "bidirectional"))
      (node (ref "DISP7") (pin "P$6") (pinfunction "ROW6+_P$6") (pintype "bidirectional"))
      (node (ref "R32") (pin "1") (pinfunction "1_1") (pintype "passive"))
    )
    (net (code "85") (name "Net-(DISP3-ROW7+)") (class "Default")
      (node (ref "DISP3") (pin "P$9") (pinfunction "ROW7+_P$9") (pintype "bidirectional"))
      (node (ref "DISP7") (pin "P$9") (pinfunction "ROW7+_P$9") (pintype "bidirectional"))
      (node (ref "R31") (pin "1") (pinfunction "1_1") (pintype "passive"))
    )
    (net (code "86") (name "Net-(DISP3-ROW8+)") (class "Default")
      (node (ref "DISP3") (pin "P$12") (pinfunction "ROW8+_P$12") (pintype "bidirectional"))
      (node (ref "DISP7") (pin "P$12") (pinfunction "ROW8+_P$12") (pintype "bidirectional"))
      (node (ref "R30") (pin "1") (pinfunction "1_1") (pintype "passive"))
    )
    (net (code "87") (name "Net-(DISP4-ROW1+)") (class "Default")
      (node (ref "DISP4") (pin "P$22") (pinfunction "ROW1+_P$22") (pintype "bidirectional"))
      (node (ref "DISP8") (pin "P$22") (pinfunction "ROW1+_P$22") (pintype "bidirectional"))
      (node (ref "R13") (pin "1") (pinfunction "1_1") (pintype "passive"))
    )
    (net (code "88") (name "Net-(DISP4-ROW2+)") (class "Default")
      (node (ref "DISP4") (pin "P$19") (pinfunction "ROW2+_P$19") (pintype "bidirectional"))
      (node (ref "DISP8") (pin "P$19") (pinfunction "ROW2+_P$19") (pintype "bidirectional"))
      (node (ref "R12") (pin "1") (pinfunction "1_1") (pintype "passive"))
    )
    (net (code "89") (name "Net-(DISP4-ROW3+)") (class "Default")
      (node (ref "DISP4") (pin "P$16") (pinfunction "ROW3+_P$16") (pintype "bidirectional"))
      (node (ref "DISP8") (pin "P$16") (pinfunction "ROW3+_P$16") (pintype "bidirectional"))
      (node (ref "R11") (pin "1") (pinfunction "1_1") (pintype "passive"))
    )
    (net (code "90") (name "Net-(DISP4-ROW4+)") (class "Default")
      (node (ref "DISP4") (pin "P$13") (pinfunction "ROW4+_P$13") (pintype "bidirectional"))
      (node (ref "DISP8") (pin "P$13") (pinfunction "ROW4+_P$13") (pintype "bidirectional"))
      (node (ref "R10") (pin "1") (pinfunction "1_1") (pintype "passive"))
    )
    (net (code "91") (name "Net-(DISP4-ROW5+)") (class "Default")
      (node (ref "DISP4") (pin "P$3") (pinfunction "ROW5+_P$3") (pintype "bidirectional"))
      (node (ref "DISP8") (pin "P$3") (pinfunction "ROW5+_P$3") (pintype "bidirectional"))
      (node (ref "R29") (pin "1") (pinfunction "1_1") (pintype "passive"))
    )
    (net (code "92") (name "Net-(DISP4-ROW6+)") (class "Default")
      (node (ref "DISP4") (pin "P$6") (pinfunction "ROW6+_P$6") (pintype "bidirectional"))
      (node (ref "DISP8") (pin "P$6") (pinfunction "ROW6+_P$6") (pintype "bidirectional"))
      (node (ref "R28") (pin "1") (pinfunction "1_1") (pintype "passive"))
    )
    (net (code "93") (name "Net-(DISP4-ROW7+)") (class "Default")
      (node (ref "DISP4") (pin "P$9") (pinfunction "ROW7+_P$9") (pintype "bidirectional"))
      (node (ref "DISP8") (pin "P$9") (pinfunction "ROW7+_P$9") (pintype "bidirectional"))
      (node (ref "R27") (pin "1") (pinfunction "1_1") (pintype "passive"))
    )
    (net (code "94") (name "Net-(DISP4-ROW8+)") (class "Default")
      (node (ref "DISP4") (pin "P$12") (pinfunction "ROW8+_P$12") (pintype "bidirectional"))
      (node (ref "DISP8") (pin "P$12") (pinfunction "ROW8+_P$12") (pintype "bidirectional"))
      (node (ref "R26") (pin "1") (pinfunction "1_1") (pintype "passive"))
    )
    (net (code "95") (name "Net-(IC1-PTB6)") (class "Default")
      (node (ref "C11") (pin "2") (pinfunction "2_2") (pintype "passive"))
      (node (ref "IC1") (pin "12") (pinfunction "PTB6_12") (pintype "bidirectional"))
      (node (ref "R6") (pin "1") (pinfunction "1_1") (pintype "passive"))
      (node (ref "XTL1") (pin "1") (pinfunction "1_1") (pintype "passive"))
    )
    (net (code "96") (name "Net-(IC1-PTB7)") (class "Default")
      (node (ref "C2") (pin "2") (pinfunction "2_2") (pintype "passive"))
      (node (ref "IC1") (pin "11") (pinfunction "PTB7_11") (pintype "bidirectional"))
      (node (ref "R6") (pin "2") (pinfunction "2_2") (pintype "passive"))
      (node (ref "XTL1") (pin "2") (pinfunction "2_2") (pintype "passive"))
    )
    (net (code "97") (name "Net-(IC1-PTD6)") (class "Default")
      (node (ref "IC1") (pin "23") (pinfunction "PTD6_23") (pintype "bidirectional"))
      (node (ref "PD6") (pin "TP") (pinfunction "TP_TP") (pintype "input"))
    )
    (net (code "98") (name "Net-(IC1-PTD7)") (class "Default")
      (node (ref "IC1") (pin "22") (pinfunction "PTD7_22") (pintype "bidirectional"))
      (node (ref "PD7") (pin "TP") (pinfunction "TP_TP") (pintype "input"))
    )
    (net (code "99") (name "Net-(IC1-PTE6)") (class "Default")
      (node (ref "IC1") (pin "16") (pinfunction "PTE6_16") (pintype "bidirectional"))
      (node (ref "PE6") (pin "TP") (pinfunction "TP_TP") (pintype "input"))
    )
    (net (code "100") (name "Net-(IC1-PTF4)") (class "Default")
      (node (ref "IC1") (pin "30") (pinfunction "PTF4_30") (pintype "bidirectional"))
      (node (ref "PF4") (pin "TP") (pinfunction "TP_TP") (pintype "input"))
    )
    (net (code "101") (name "Net-(IC1-PTF5)") (class "Default")
      (node (ref "IC1") (pin "29") (pinfunction "PTF5_29") (pintype "bidirectional"))
      (node (ref "PF5") (pin "TP") (pinfunction "TP_TP") (pintype "input"))
    )
    (net (code "102") (name "Net-(IC1-PTF6)") (class "Default")
      (node (ref "IC1") (pin "28") (pinfunction "PTF6_28") (pintype "bidirectional"))
      (node (ref "PF6") (pin "TP") (pinfunction "TP_TP") (pintype "input"))
    )
    (net (code "103") (name "Net-(IC1-PTF7)") (class "Default")
      (node (ref "IC1") (pin "27") (pinfunction "PTF7_27") (pintype "bidirectional"))
      (node (ref "PF7") (pin "TP") (pinfunction "TP_TP") (pintype "input"))
    )
    (net (code "104") (name "Net-(IC1-PTG0)") (class "Default")
      (node (ref "IC1") (pin "58") (pinfunction "PTG0_58") (pintype "bidirectional"))
      (node (ref "PG0") (pin "TP") (pinfunction "TP_TP") (pintype "input"))
    )
    (net (code "105") (name "Net-(IC1-PTG1)") (class "Default")
      (node (ref "IC1") (pin "57") (pinfunction "PTG1_57") (pintype "bidirectional"))
      (node (ref "PG1") (pin "TP") (pinfunction "TP_TP") (pintype "input"))
    )
    (net (code "106") (name "Net-(IC1-PTG2)") (class "Default")
      (node (ref "IC1") (pin "56") (pinfunction "PTG2_56") (pintype "bidirectional"))
      (node (ref "PG2") (pin "TP") (pinfunction "TP_TP") (pintype "input"))
    )
    (net (code "107") (name "Net-(IC1-PTH0)") (class "Default")
      (node (ref "IC1") (pin "15") (pinfunction "PTH0_15") (pintype "bidirectional"))
      (node (ref "PH0") (pin "TP") (pinfunction "TP_TP") (pintype "input"))
    )
    (net (code "108") (name "Net-(IC1-PTH1)") (class "Default")
      (node (ref "IC1") (pin "14") (pinfunction "PTH1_14") (pintype "bidirectional"))
      (node (ref "PH1") (pin "TP") (pinfunction "TP_TP") (pintype "input"))
    )
    (net (code "109") (name "Net-(IC1-PTH6)") (class "Default")
      (node (ref "IC1") (pin "4") (pinfunction "PTH6_4") (pintype "bidirectional"))
      (node (ref "PH6") (pin "TP") (pinfunction "TP_TP") (pintype "input"))
    )
    (net (code "110") (name "Net-(IC1-PTH7)") (class "Default")
      (node (ref "IC1") (pin "3") (pinfunction "PTH7_3") (pintype "bidirectional"))
      (node (ref "PH7") (pin "TP") (pinfunction "TP_TP") (pintype "input"))
    )
    (net (code "111") (name "Net-(IC3A-QA)") (class "Default")
      (node (ref "IC3") (pin "15") (pinfunction "QA_15") (pintype "tri_state"))
      (node (ref "R13") (pin "2") (pinfunction "2_2") (pintype "passive"))
    )
    (net (code "112") (name "Net-(IC3A-QB)") (class "Default")
      (node (ref "IC3") (pin "1") (pinfunction "QB_1") (pintype "tri_state"))
      (node (ref "R12") (pin "2") (pinfunction "2_2") (pintype "passive"))
    )
    (net (code "113") (name "Net-(IC3A-QC)") (class "Default")
      (node (ref "IC3") (pin "2") (pinfunction "QC_2") (pintype "tri_state"))
      (node (ref "R11") (pin "2") (pinfunction "2_2") (pintype "passive"))
    )
    (net (code "114") (name "Net-(IC3A-QD)") (class "Default")
      (node (ref "IC3") (pin "3") (pinfunction "QD_3") (pintype "tri_state"))
      (node (ref "R10") (pin "2") (pinfunction "2_2") (pintype "passive"))
    )
    (net (code "115") (name "Net-(IC3A-QE)") (class "Default")
      (node (ref "IC3") (pin "4") (pinfunction "QE_4") (pintype "tri_state"))
      (node (ref "R29") (pin "2") (pinfunction "2_2") (pintype "passive"))
    )
    (net (code "116") (name "Net-(IC3A-QF)") (class "Default")
      (node (ref "IC3") (pin "5") (pinfunction "QF_5") (pintype "tri_state"))
      (node (ref "R28") (pin "2") (pinfunction "2_2") (pintype "passive"))
    )
    (net (code "117") (name "Net-(IC3A-QG)") (class "Default")
      (node (ref "IC3") (pin "6") (pinfunction "QG_6") (pintype "tri_state"))
      (node (ref "R27") (pin "2") (pinfunction "2_2") (pintype "passive"))
    )
    (net (code "118") (name "Net-(IC3A-QH)") (class "Default")
      (node (ref "IC3") (pin "7") (pinfunction "QH_7") (pintype "tri_state"))
      (node (ref "R26") (pin "2") (pinfunction "2_2") (pintype "passive"))
    )
    (net (code "119") (name "Net-(IC3A-SER)") (class "Default")
      (node (ref "IC3") (pin "14") (pinfunction "SER_14") (pintype "input"))
      (node (ref "IC4") (pin "9") (pinfunction "QH*_9") (pintype "tri_state"))
    )
    (net (code "120") (name "Net-(IC4A-QA)") (class "Default")
      (node (ref "IC4") (pin "15") (pinfunction "QA_15") (pintype "tri_state"))
      (node (ref "R17") (pin "2") (pinfunction "2_2") (pintype "passive"))
    )
    (net (code "121") (name "Net-(IC4A-QB)") (class "Default")
      (node (ref "IC4") (pin "1") (pinfunction "QB_1") (pintype "tri_state"))
      (node (ref "R16") (pin "2") (pinfunction "2_2") (pintype "passive"))
    )
    (net (code "122") (name "Net-(IC4A-QC)") (class "Default")
      (node (ref "IC4") (pin "2") (pinfunction "QC_2") (pintype "tri_state"))
      (node (ref "R15") (pin "2") (pinfunction "2_2") (pintype "passive"))
    )
    (net (code "123") (name "Net-(IC4A-QD)") (class "Default")
      (node (ref "IC4") (pin "3") (pinfunction "QD_3") (pintype "tri_state"))
      (node (ref "R14") (pin "2") (pinfunction "2_2") (pintype "passive"))
    )
    (net (code "124") (name "Net-(IC4A-QE)") (class "Default")
      (node (ref "IC4") (pin "4") (pinfunction "QE_4") (pintype "tri_state"))
      (node (ref "R33") (pin "2") (pinfunction "2_2") (pintype "passive"))
    )
    (net (code "125") (name "Net-(IC4A-QF)") (class "Default")
      (node (ref "IC4") (pin "5") (pinfunction "QF_5") (pintype "tri_state"))
      (node (ref "R32") (pin "2") (pinfunction "2_2") (pintype "passive"))
    )
    (net (code "126") (name "Net-(IC4A-QG)") (class "Default")
      (node (ref "IC4") (pin "6") (pinfunction "QG_6") (pintype "tri_state"))
      (node (ref "R31") (pin "2") (pinfunction "2_2") (pintype "passive"))
    )
    (net (code "127") (name "Net-(IC4A-QH)") (class "Default")
      (node (ref "IC4") (pin "7") (pinfunction "QH_7") (pintype "tri_state"))
      (node (ref "R30") (pin "2") (pinfunction "2_2") (pintype "passive"))
    )
    (net (code "128") (name "Net-(IC4A-SER)") (class "Default")
      (node (ref "IC4") (pin "14") (pinfunction "SER_14") (pintype "input"))
      (node (ref "IC5") (pin "9") (pinfunction "QH*_9") (pintype "tri_state"))
    )
    (net (code "129") (name "Net-(IC5A-QA)") (class "Default")
      (node (ref "IC5") (pin "15") (pinfunction "QA_15") (pintype "tri_state"))
      (node (ref "R21") (pin "2") (pinfunction "2_2") (pintype "passive"))
    )
    (net (code "130") (name "Net-(IC5A-QB)") (class "Default")
      (node (ref "IC5") (pin "1") (pinfunction "QB_1") (pintype "tri_state"))
      (node (ref "R20") (pin "2") (pinfunction "2_2") (pintype "passive"))
    )
    (net (code "131") (name "Net-(IC5A-QC)") (class "Default")
      (node (ref "IC5") (pin "2") (pinfunction "QC_2") (pintype "tri_state"))
      (node (ref "R19") (pin "2") (pinfunction "2_2") (pintype "passive"))
    )
    (net (code "132") (name "Net-(IC5A-QD)") (class "Default")
      (node (ref "IC5") (pin "3") (pinfunction "QD_3") (pintype "tri_state"))
      (node (ref "R18") (pin "2") (pinfunction "2_2") (pintype "passive"))
    )
    (net (code "133") (name "Net-(IC5A-QE)") (class "Default")
      (node (ref "IC5") (pin "4") (pinfunction "QE_4") (pintype "tri_state"))
      (node (ref "R37") (pin "2") (pinfunction "2_2") (pintype "passive"))
    )
    (net (code "134") (name "Net-(IC5A-QF)") (class "Default")
      (node (ref "IC5") (pin "5") (pinfunction "QF_5") (pintype "tri_state"))
      (node (ref "R36") (pin "2") (pinfunction "2_2") (pintype "passive"))
    )
    (net (code "135") (name "Net-(IC5A-QG)") (class "Default")
      (node (ref "IC5") (pin "6") (pinfunction "QG_6") (pintype "tri_state"))
      (node (ref "R35") (pin "2") (pinfunction "2_2") (pintype "passive"))
    )
    (net (code "136") (name "Net-(IC5A-QH)") (class "Default")
      (node (ref "IC5") (pin "7") (pinfunction "QH_7") (pintype "tri_state"))
      (node (ref "R34") (pin "2") (pinfunction "2_2") (pintype "passive"))
    )
    (net (code "137") (name "Net-(IC5A-SER)") (class "Default")
      (node (ref "IC5") (pin "14") (pinfunction "SER_14") (pintype "input"))
      (node (ref "IC6") (pin "9") (pinfunction "QH*_9") (pintype "tri_state"))
    )
    (net (code "138") (name "Net-(IC6A-QA)") (class "Default")
      (node (ref "IC6") (pin "15") (pinfunction "QA_15") (pintype "tri_state"))
      (node (ref "R25") (pin "2") (pinfunction "2_2") (pintype "passive"))
    )
    (net (code "139") (name "Net-(IC6A-QB)") (class "Default")
      (node (ref "IC6") (pin "1") (pinfunction "QB_1") (pintype "tri_state"))
      (node (ref "R24") (pin "2") (pinfunction "2_2") (pintype "passive"))
    )
    (net (code "140") (name "Net-(IC6A-QC)") (class "Default")
      (node (ref "IC6") (pin "2") (pinfunction "QC_2") (pintype "tri_state"))
      (node (ref "R23") (pin "2") (pinfunction "2_2") (pintype "passive"))
    )
    (net (code "141") (name "Net-(IC6A-QD)") (class "Default")
      (node (ref "IC6") (pin "3") (pinfunction "QD_3") (pintype "tri_state"))
      (node (ref "R22") (pin "2") (pinfunction "2_2") (pintype "passive"))
    )
    (net (code "142") (name "Net-(IC6A-QE)") (class "Default")
      (node (ref "IC6") (pin "4") (pinfunction "QE_4") (pintype "tri_state"))
      (node (ref "R41") (pin "2") (pinfunction "2_2") (pintype "passive"))
    )
    (net (code "143") (name "Net-(IC6A-QF)") (class "Default")
      (node (ref "IC6") (pin "5") (pinfunction "QF_5") (pintype "tri_state"))
      (node (ref "R40") (pin "2") (pinfunction "2_2") (pintype "passive"))
    )
    (net (code "144") (name "Net-(IC6A-QG)") (class "Default")
      (node (ref "IC6") (pin "6") (pinfunction "QG_6") (pintype "tri_state"))
      (node (ref "R39") (pin "2") (pinfunction "2_2") (pintype "passive"))
    )
    (net (code "145") (name "Net-(IC6A-QH)") (class "Default")
      (node (ref "IC6") (pin "7") (pinfunction "QH_7") (pintype "tri_state"))
      (node (ref "R38") (pin "2") (pinfunction "2_2") (pintype "passive"))
    )
    (net (code "146") (name "Net-(IC7-DS)") (class "Default")
      (node (ref "IC7") (pin "2") (pinfunction "DS_2") (pintype "input"))
      (node (ref "IC8") (pin "9") (pinfunction "Q7S_9") (pintype "output"))
    )
    (net (code "147") (name "Net-(LED1-C)") (class "Default")
      (node (ref "LED1") (pin "K") (pinfunction "C_K") (pintype "passive"))
      (node (ref "R9") (pin "2") (pinfunction "2_2") (pintype "passive"))
    )
    (net (code "148") (name "Net-(LED2-C)") (class "Default")
      (node (ref "LED2") (pin "K") (pinfunction "C_K") (pintype "passive"))
      (node (ref "R8") (pin "2") (pinfunction "2_2") (pintype "passive"))
    )
    (net (code "149") (name "Net-(LED3-C)") (class "Default")
      (node (ref "LED3") (pin "K") (pinfunction "C_K") (pintype "passive"))
      (node (ref "R7") (pin "2") (pinfunction "2_2") (pintype "passive"))
    )
    (net (code "150") (name "unconnected-(IC1-PTE3-Pad53)") (class "Default")
      (node (ref "IC1") (pin "53") (pinfunction "PTE3_53") (pintype "bidirectional"))
    )
    (net (code "151") (name "unconnected-(IC1-PTE4-Pad39)") (class "Default")
      (node (ref "IC1") (pin "39") (pinfunction "PTE4_39") (pintype "bidirectional"))
    )
    (net (code "152") (name "unconnected-(IC1-PTE5-Pad17)") (class "Default")
      (node (ref "IC1") (pin "17") (pinfunction "PTE5_17") (pintype "bidirectional"))
    )
    (net (code "153") (name "unconnected-(IC1-PTF0-Pad43)") (class "Default")
      (node (ref "IC1") (pin "43") (pinfunction "PTF0_43") (pintype "bidirectional"))
    )
    (net (code "154") (name "unconnected-(IC1-PTF1-Pad42)") (class "Default")
      (node (ref "IC1") (pin "42") (pinfunction "PTF1_42") (pintype "bidirectional"))
    )
    (net (code "155") (name "unconnected-(IC1-PTF2-Pad36)") (class "Default")
      (node (ref "IC1") (pin "36") (pinfunction "PTF2_36") (pintype "bidirectional"))
    )
    (net (code "156") (name "unconnected-(IC1-PTF3-Pad35)") (class "Default")
      (node (ref "IC1") (pin "35") (pinfunction "PTF3_35") (pintype "bidirectional"))
    )
    (net (code "157") (name "unconnected-(IC1-PTG3-Pad55)") (class "Default")
      (node (ref "IC1") (pin "55") (pinfunction "PTG3_55") (pintype "bidirectional"))
    )
    (net (code "158") (name "unconnected-(IC1-REFL-Pad9)") (class "Default")
      (node (ref "IC1") (pin "9") (pinfunction "REFL_9") (pintype "bidirectional"))
    )
    (net (code "159") (name "unconnected-(IC3A-QH*-Pad9)") (class "Default")
      (node (ref "IC3") (pin "9") (pinfunction "QH*_9") (pintype "tri_state"))
    )
    (net (code "160") (name "unconnected-(IC7-Q7S-Pad9)") (class "Default")
      (node (ref "IC7") (pin "9") (pinfunction "Q7S_9") (pintype "output"))
    )
    (net (code "161") (name "unconnected-(SW1-P1-Pad4)") (class "Default")
      (node (ref "SW1") (pin "4") (pinfunction "P1_4") (pintype "passive"))
    )
    (net (code "162") (name "unconnected-(SW1-S1-Pad2)") (class "Default")
      (node (ref "SW1") (pin "2") (pinfunction "S1_2") (pintype "passive"))
    )
    (net (code "163") (name "unconnected-(SW2-P1-Pad4)") (class "Default")
      (node (ref "SW2") (pin "4") (pinfunction "P1_4") (pintype "passive"))
    )
    (net (code "164") (name "unconnected-(SW2-S1-Pad2)") (class "Default")
      (node (ref "SW2") (pin "2") (pinfunction "S1_2") (pintype "passive"))
    )
    (net (code "165") (name "unconnected-(SW3-P1-Pad4)") (class "Default")
      (node (ref "SW3") (pin "4") (pinfunction "P1_4") (pintype "passive"))
    )
    (net (code "166") (name "unconnected-(SW3-S1-Pad2)") (class "Default")
      (node (ref "SW3") (pin "2") (pinfunction "S1_2") (pintype "passive"))
    )
    (net (code "167") (name "unconnected-(SW4-P1-Pad4)") (class "Default")
      (node (ref "SW4") (pin "4") (pinfunction "P1_4") (pintype "passive"))
    )
    (net (code "168") (name "unconnected-(SW4-S1-Pad2)") (class "Default")
      (node (ref "SW4") (pin "2") (pinfunction "S1_2") (pintype "passive"))
    )
    (net (code "169") (name "unconnected-(SW5-P1-Pad4)") (class "Default")
      (node (ref "SW5") (pin "4") (pinfunction "P1_4") (pintype "passive"))
    )
    (net (code "170") (name "unconnected-(SW5-S1-Pad2)") (class "Default")
      (node (ref "SW5") (pin "2") (pinfunction "S1_2") (pintype "passive"))
    )
    (net (code "171") (name "unconnected-(SW6-P1-Pad4)") (class "Default")
      (node (ref "SW6") (pin "4") (pinfunction "P1_4") (pintype "passive"))
    )
    (net (code "172") (name "unconnected-(SW6-S1-Pad2)") (class "Default")
      (node (ref "SW6") (pin "2") (pinfunction "S1_2") (pintype "passive"))
    )
    (net (code "173") (name "unconnected-(SW7-P1-Pad4)") (class "Default")
      (node (ref "SW7") (pin "4") (pinfunction "P1_4") (pintype "passive"))
    )
    (net (code "174") (name "unconnected-(SW7-S1-Pad2)") (class "Default")
      (node (ref "SW7") (pin "2") (pinfunction "S1_2") (pintype "passive"))
    )
    (net (code "175") (name "unconnected-(SW8-P1-Pad4)") (class "Default")
      (node (ref "SW8") (pin "4") (pinfunction "P1_4") (pintype "passive"))
    )
    (net (code "176") (name "unconnected-(SW8-S1-Pad2)") (class "Default")
      (node (ref "SW8") (pin "2") (pinfunction "S1_2") (pintype "passive"))
    )
    (net (code "177") (name "unconnected-(SW9-P-Pad3)") (class "Default")
      (node (ref "SW9") (pin "3") (pinfunction "P_3") (pintype "passive"))
    )
    (net (code "178") (name "unconnected-(SW9-S1-Pad2)") (class "Default")
      (node (ref "SW9") (pin "2") (pinfunction "S1_2") (pintype "passive"))
    )
    (net (code "179") (name "unconnected-(SW10-P-Pad3)") (class "Default")
      (node (ref "SW10") (pin "3") (pinfunction "P_3") (pintype "passive"))
    )
    (net (code "180") (name "unconnected-(SW10-S1-Pad2)") (class "Default")
      (node (ref "SW10") (pin "2") (pinfunction "S1_2") (pintype "passive"))
    )
    (net (code "181") (name "unconnected-(SW11-P-Pad3)") (class "Default")
      (node (ref "SW11") (pin "3") (pinfunction "P_3") (pintype "passive"))
    )
    (net (code "182") (name "unconnected-(SW11-S1-Pad2)") (class "Default")
      (node (ref "SW11") (pin "2") (pinfunction "S1_2") (pintype "passive"))
    )
  )
)
